# 10-Sensing.net
KiCad netlist of a schematic drawn in Altium Designer
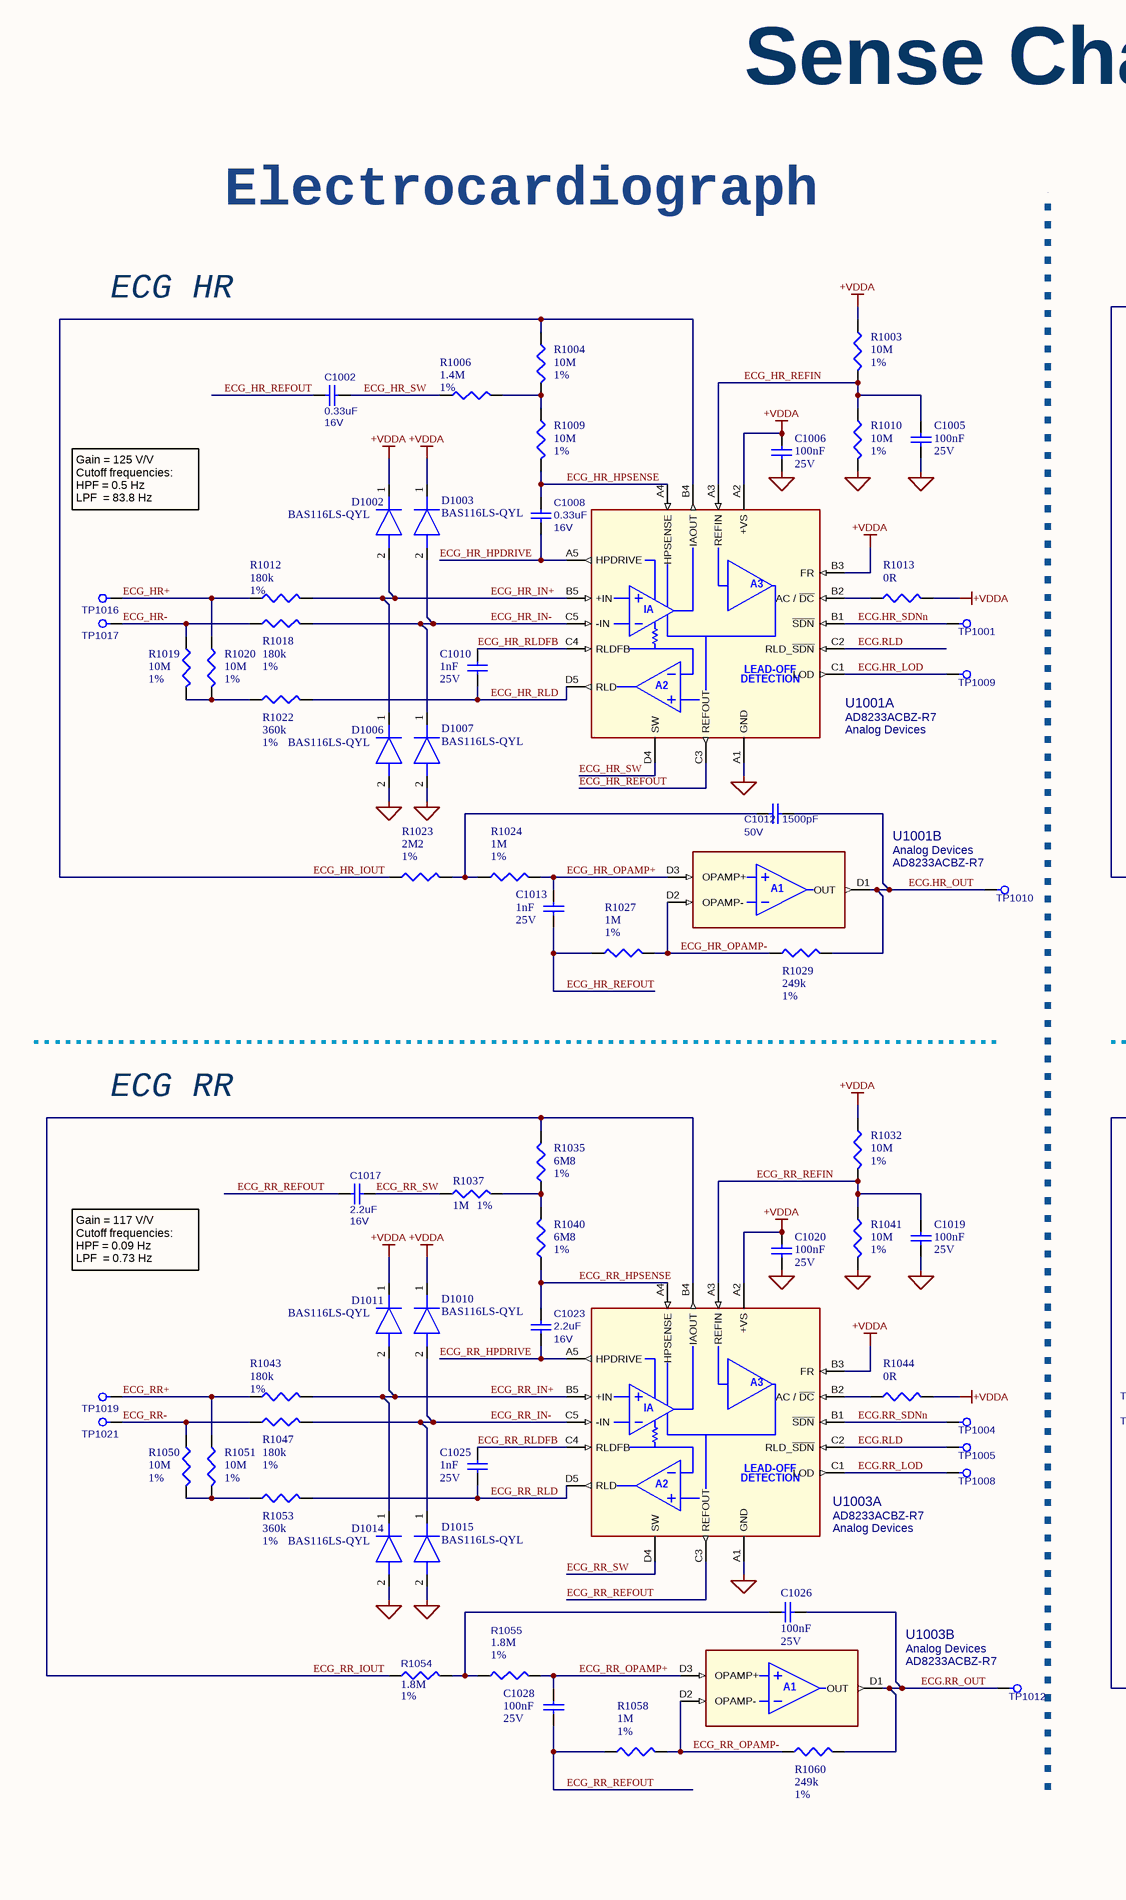
[diagram p0: 10-Sensing.SchDoc, left]
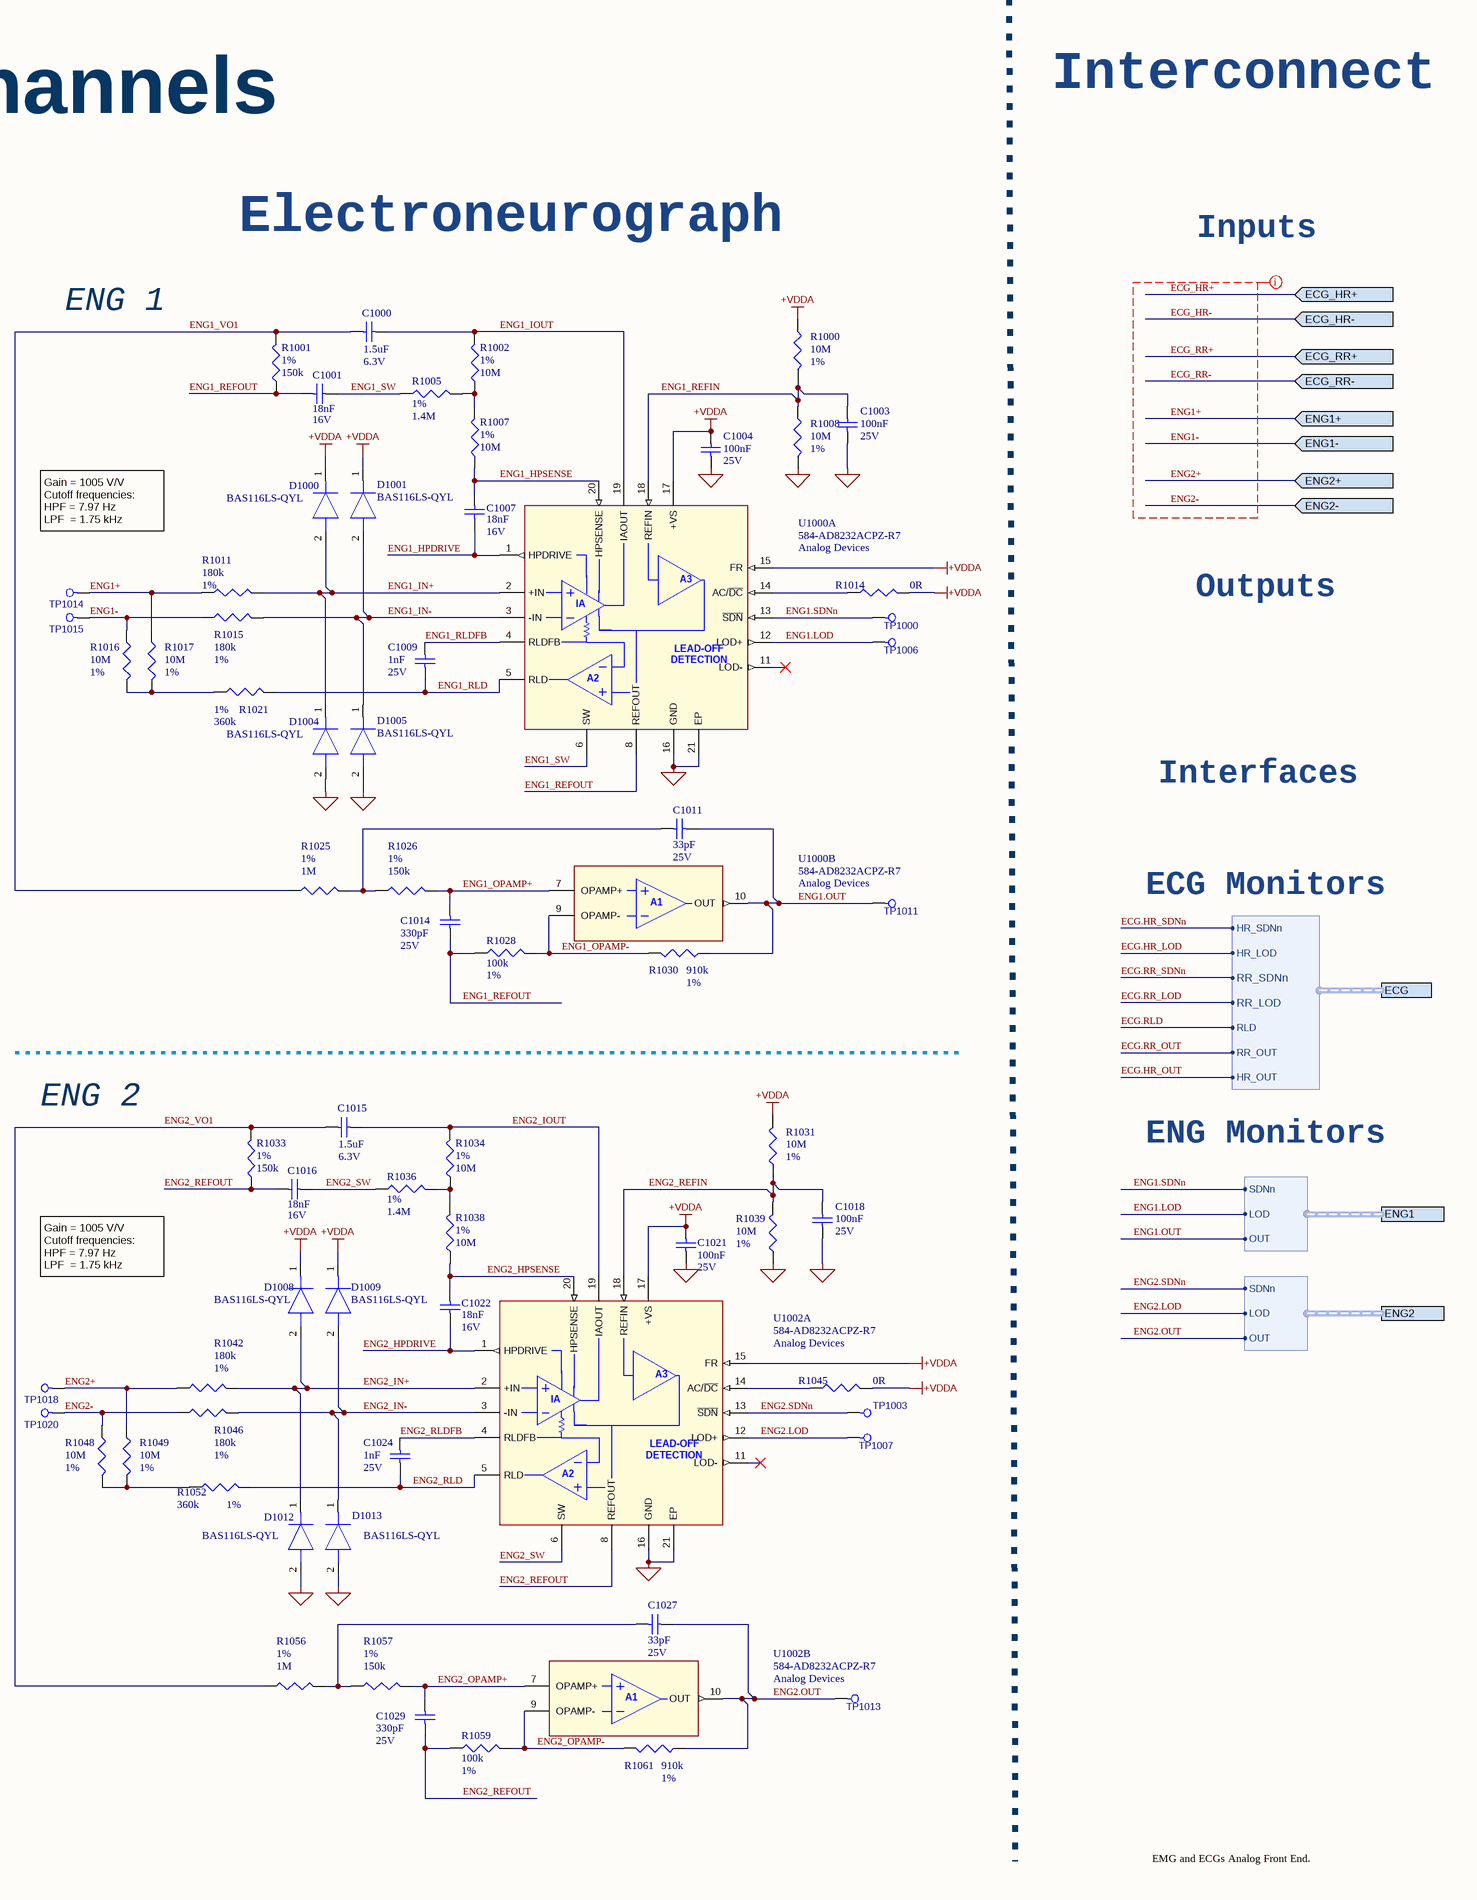
[diagram p1: 10-Sensing.SchDoc, right]

(export (version "E")
  (design (tool "Eeschema 10.0.6"))
  (components
    (comp (ref "C1000")
      (value "1.5uF")
      (footprint "C0201_C")
      (fields
        (field (name "MANUFACTURER") "Murata")
        (field (name "MANUFACTURER PART NUMBER") "GRM033R60J155ME14D")
        (field (name "RATED DC VOLTAGE (URDC)") "6.3V")
      )
      (libsource (lib "MP-LIBRARY") (part "GRM033R60J155ME14D"))
    )
    (comp (ref "C1001")
      (value "18nF")
      (footprint "C0201_C")
      (fields
        (field (name "MANUFACTURER") "Murata")
        (field (name "MANUFACTURER PART NUMBER") "GRM033R61C183KE84D")
        (field (name "RATED DC VOLTAGE (URDC)") "16V")
      )
      (libsource (lib "MP-LIBRARY") (part "GRM033R61C183KE84D"))
    )
    (comp (ref "C1002")
      (value "0.33uF")
      (footprint "CAP0402_REDUCED")
      (description "Capacitor, 0.33uF, X7S, 16V, 10%, 0402")
      (fields
        (field (name "MANUFACTURER") "TDK")
        (field (name "RATING") "16V")
        (field (name "MANUFACTURER PART NUMBER") "CGA2B1X7S1C334K050BC")
      )
      (libsource (lib "MP-LIBRARY") (part "CGA2B1X7S1C334K050BC"))
    )
    (comp (ref "C1003")
      (value "100nF")
      (footprint "C0201_C")
      (fields
        (field (name "MANUFACTURER") "Murata")
        (field (name "MANUFACTURER PART NUMBER") "GRM033R61E104KE14J")
        (field (name "RATED DC VOLTAGE (URDC)") "25V")
      )
      (libsource (lib "MP-LIBRARY") (part "GRM033R61E104KE14J"))
    )
    (comp (ref "C1004")
      (value "100nF")
      (footprint "C0201_C")
      (fields
        (field (name "MANUFACTURER") "Murata")
        (field (name "MANUFACTURER PART NUMBER") "GRM033R61E104KE14J")
        (field (name "RATED DC VOLTAGE (URDC)") "25V")
      )
      (libsource (lib "MP-LIBRARY") (part "GRM033R61E104KE14J"))
    )
    (comp (ref "C1005")
      (value "100nF")
      (footprint "C0201_C")
      (fields
        (field (name "MANUFACTURER") "Murata")
        (field (name "MANUFACTURER PART NUMBER") "GRM033R61E104KE14J")
        (field (name "RATED DC VOLTAGE (URDC)") "25V")
      )
      (libsource (lib "MP-LIBRARY") (part "GRM033R61E104KE14J"))
    )
    (comp (ref "C1006")
      (value "100nF")
      (footprint "C0201_C")
      (fields
        (field (name "MANUFACTURER") "Murata")
        (field (name "MANUFACTURER PART NUMBER") "GRM033R61E104KE14J")
        (field (name "RATED DC VOLTAGE (URDC)") "25V")
      )
      (libsource (lib "MP-LIBRARY") (part "GRM033R61E104KE14J"))
    )
    (comp (ref "C1007")
      (value "18nF")
      (footprint "C0201_C")
      (fields
        (field (name "MANUFACTURER") "Murata")
        (field (name "MANUFACTURER PART NUMBER") "GRM033R61C183KE84D")
        (field (name "RATED DC VOLTAGE (URDC)") "16V")
      )
      (libsource (lib "MP-LIBRARY") (part "GRM033R61C183KE84D"))
    )
    (comp (ref "C1008")
      (value "0.33uF")
      (footprint "CAP0402_REDUCED")
      (description "Capacitor, 0.33uF, X7S, 16V, 10%, 0402")
      (fields
        (field (name "MANUFACTURER") "TDK")
        (field (name "RATING") "16V")
        (field (name "MANUFACTURER PART NUMBER") "CGA2B1X7S1C334K050BC")
      )
      (libsource (lib "MP-LIBRARY") (part "CGA2B1X7S1C334K050BC"))
    )
    (comp (ref "C1009")
      (value "1nF")
      (footprint "C0201_C")
      (fields
        (field (name "MANUFACTURER") "Murata")
        (field (name "MANUFACTURER PART NUMBER") "GRM033R71E102KA01J")
        (field (name "RATED DC VOLTAGE (URDC)") "25V")
      )
      (libsource (lib "MP-LIBRARY") (part "GRM033R71E102KA01J"))
    )
    (comp (ref "C1010")
      (value "1nF")
      (footprint "C0201_C")
      (fields
        (field (name "MANUFACTURER") "Murata")
        (field (name "MANUFACTURER PART NUMBER") "GRM033R71E102KA01J")
        (field (name "RATED DC VOLTAGE (URDC)") "25V")
      )
      (libsource (lib "MP-LIBRARY") (part "GRM033R71E102KA01J"))
    )
    (comp (ref "C1011")
      (value "33pF")
      (footprint "C0201_C")
      (fields
        (field (name "MANUFACTURER") "Murata")
        (field (name "MANUFACTURER PART NUMBER") "GRM0335C1E330JA01D")
        (field (name "RATED DC VOLTAGE (URDC)") "25V")
      )
      (libsource (lib "MP-LIBRARY") (part "GRM0335C1E330JA01D"))
    )
    (comp (ref "C1012")
      (value "1500pF")
      (footprint "CAP0402_REDUCED")
      (description "Capacitor, 1500pF, X7R, 50V, 10%, 0402")
      (fields
        (field (name "MANUFACTURER") "Murata")
        (field (name "RATING") "50V")
        (field (name "MANUFACTURER PART NUMBER") "GCM155R71H152KA37D")
      )
      (libsource (lib "MP-LIBRARY") (part "GCM155R71H152KA37D"))
    )
    (comp (ref "C1013")
      (value "1nF")
      (footprint "C0201_C")
      (fields
        (field (name "MANUFACTURER") "Murata")
        (field (name "MANUFACTURER PART NUMBER") "GRM033R71E102KA01J")
        (field (name "RATED DC VOLTAGE (URDC)") "25V")
      )
      (libsource (lib "MP-LIBRARY") (part "GRM033R71E102KA01J"))
    )
    (comp (ref "C1014")
      (value "330pF")
      (footprint "C0201_C")
      (fields
        (field (name "MANUFACTURER") "Murata")
        (field (name "MANUFACTURER PART NUMBER") "GRM033R71E331KA01D")
        (field (name "RATED DC VOLTAGE (URDC)") "25V")
      )
      (libsource (lib "MP-LIBRARY") (part "GRM033R71E331KA01D"))
    )
    (comp (ref "C1015")
      (value "1.5uF")
      (footprint "C0201_C")
      (fields
        (field (name "MANUFACTURER") "Murata")
        (field (name "MANUFACTURER PART NUMBER") "GRM033R60J155ME14D")
        (field (name "RATED DC VOLTAGE (URDC)") "6.3V")
      )
      (libsource (lib "MP-LIBRARY") (part "GRM033R60J155ME14D"))
    )
    (comp (ref "C1016")
      (value "18nF")
      (footprint "C0201_C")
      (fields
        (field (name "MANUFACTURER") "Murata")
        (field (name "MANUFACTURER PART NUMBER") "GRM033R61C183KE84D")
        (field (name "RATED DC VOLTAGE (URDC)") "16V")
      )
      (libsource (lib "MP-LIBRARY") (part "GRM033R61C183KE84D"))
    )
    (comp (ref "C1017")
      (value "2.2uF")
      (footprint "CAP0603_REDUCED")
      (description "Capacitor, 2.2uF, X7R, 16V, 10%, 0603, Implant-grade")
      (fields
        (field (name "MANUFACTURER") "Murata")
        (field (name "RATING") "16V")
        (field (name "MANUFACTURER PART NUMBER") "GRM188Z71C225ME43J")
      )
      (libsource (lib "MP-LIBRARY") (part "GRM188Z71C225ME43J"))
    )
    (comp (ref "C1018")
      (value "100nF")
      (footprint "C0201_C")
      (fields
        (field (name "MANUFACTURER") "Murata")
        (field (name "MANUFACTURER PART NUMBER") "GRM033R61E104KE14J")
        (field (name "RATED DC VOLTAGE (URDC)") "25V")
      )
      (libsource (lib "MP-LIBRARY") (part "GRM033R61E104KE14J"))
    )
    (comp (ref "C1019")
      (value "100nF")
      (footprint "C0201_C")
      (fields
        (field (name "MANUFACTURER") "Murata")
        (field (name "MANUFACTURER PART NUMBER") "GRM033R61E104KE14J")
        (field (name "RATED DC VOLTAGE (URDC)") "25V")
      )
      (libsource (lib "MP-LIBRARY") (part "GRM033R61E104KE14J"))
    )
    (comp (ref "C1020")
      (value "100nF")
      (footprint "C0201_C")
      (fields
        (field (name "MANUFACTURER") "Murata")
        (field (name "MANUFACTURER PART NUMBER") "GRM033R61E104KE14J")
        (field (name "RATED DC VOLTAGE (URDC)") "25V")
      )
      (libsource (lib "MP-LIBRARY") (part "GRM033R61E104KE14J"))
    )
    (comp (ref "C1021")
      (value "100nF")
      (footprint "C0201_C")
      (fields
        (field (name "MANUFACTURER") "Murata")
        (field (name "MANUFACTURER PART NUMBER") "GRM033R61E104KE14J")
        (field (name "RATED DC VOLTAGE (URDC)") "25V")
      )
      (libsource (lib "MP-LIBRARY") (part "GRM033R61E104KE14J"))
    )
    (comp (ref "C1022")
      (value "18nF")
      (footprint "C0201_C")
      (fields
        (field (name "MANUFACTURER") "Murata")
        (field (name "MANUFACTURER PART NUMBER") "GRM033R61C183KE84D")
        (field (name "RATED DC VOLTAGE (URDC)") "16V")
      )
      (libsource (lib "MP-LIBRARY") (part "GRM033R61C183KE84D"))
    )
    (comp (ref "C1023")
      (value "2.2uF")
      (footprint "CAP0603_REDUCED")
      (description "Capacitor, 2.2uF, X7R, 16V, 10%, 0603, Implant-grade")
      (fields
        (field (name "MANUFACTURER") "Murata")
        (field (name "RATING") "16V")
        (field (name "MANUFACTURER PART NUMBER") "GRM188Z71C225ME43J")
      )
      (libsource (lib "MP-LIBRARY") (part "GRM188Z71C225ME43J"))
    )
    (comp (ref "C1024")
      (value "1nF")
      (footprint "C0201_C")
      (fields
        (field (name "MANUFACTURER") "Murata")
        (field (name "MANUFACTURER PART NUMBER") "GRM033R71E102KA01J")
        (field (name "RATED DC VOLTAGE (URDC)") "25V")
      )
      (libsource (lib "MP-LIBRARY") (part "GRM033R71E102KA01J"))
    )
    (comp (ref "C1025")
      (value "1nF")
      (footprint "C0201_C")
      (fields
        (field (name "MANUFACTURER") "Murata")
        (field (name "MANUFACTURER PART NUMBER") "GRM033R71E102KA01J")
        (field (name "RATED DC VOLTAGE (URDC)") "25V")
      )
      (libsource (lib "MP-LIBRARY") (part "GRM033R71E102KA01J"))
    )
    (comp (ref "C1026")
      (value "100nF")
      (footprint "C0201_C")
      (fields
        (field (name "MANUFACTURER") "Murata")
        (field (name "MANUFACTURER PART NUMBER") "GRM033R61E104KE14J")
        (field (name "RATED DC VOLTAGE (URDC)") "25V")
      )
      (libsource (lib "MP-LIBRARY") (part "GRM033R61E104KE14J"))
    )
    (comp (ref "C1027")
      (value "33pF")
      (footprint "C0201_C")
      (fields
        (field (name "MANUFACTURER") "Murata")
        (field (name "MANUFACTURER PART NUMBER") "GRM0335C1E330JA01D")
        (field (name "RATED DC VOLTAGE (URDC)") "25V")
      )
      (libsource (lib "MP-LIBRARY") (part "GRM0335C1E330JA01D"))
    )
    (comp (ref "C1028")
      (value "100nF")
      (footprint "C0201_C")
      (fields
        (field (name "MANUFACTURER") "Murata")
        (field (name "MANUFACTURER PART NUMBER") "GRM033R61E104KE14J")
        (field (name "RATED DC VOLTAGE (URDC)") "25V")
      )
      (libsource (lib "MP-LIBRARY") (part "GRM033R61E104KE14J"))
    )
    (comp (ref "C1029")
      (value "330pF")
      (footprint "C0201_C")
      (fields
        (field (name "MANUFACTURER") "Murata")
        (field (name "MANUFACTURER PART NUMBER") "GRM033R71E331KA01D")
        (field (name "RATED DC VOLTAGE (URDC)") "25V")
      )
      (libsource (lib "MP-LIBRARY") (part "GRM033R71E331KA01D"))
    )
    (comp (ref "D1000")
      (value "BAS116LS-QYL")
      (footprint "BAS116LSQYL")
      (description "Diode")
      (fields (field (name "MOUSER PART NUMBER") "771-BAS116LS-QYL") (field (name "MANUFACTURER") "Nexperia"))
      (libsource (lib "MP-LIBRARY") (part "BAS116LS-QYL"))
    )
    (comp (ref "D1001")
      (value "BAS116LS-QYL")
      (footprint "BAS116LSQYL")
      (description "Diode")
      (fields (field (name "MOUSER PART NUMBER") "771-BAS116LS-QYL") (field (name "MANUFACTURER") "Nexperia"))
      (libsource (lib "MP-LIBRARY") (part "BAS116LS-QYL"))
    )
    (comp (ref "D1002")
      (value "BAS116LS-QYL")
      (footprint "BAS116LSQYL")
      (description "Diode")
      (fields (field (name "MOUSER PART NUMBER") "771-BAS116LS-QYL") (field (name "MANUFACTURER") "Nexperia"))
      (libsource (lib "MP-LIBRARY") (part "BAS116LS-QYL"))
    )
    (comp (ref "D1003")
      (value "BAS116LS-QYL")
      (footprint "BAS116LSQYL")
      (description "Diode")
      (fields (field (name "MOUSER PART NUMBER") "771-BAS116LS-QYL") (field (name "MANUFACTURER") "Nexperia"))
      (libsource (lib "MP-LIBRARY") (part "BAS116LS-QYL"))
    )
    (comp (ref "D1004")
      (value "BAS116LS-QYL")
      (footprint "BAS116LSQYL")
      (description "Diode")
      (fields (field (name "MOUSER PART NUMBER") "771-BAS116LS-QYL") (field (name "MANUFACTURER") "Nexperia"))
      (libsource (lib "MP-LIBRARY") (part "BAS116LS-QYL"))
    )
    (comp (ref "D1005")
      (value "BAS116LS-QYL")
      (footprint "BAS116LSQYL")
      (description "Diode")
      (fields (field (name "MOUSER PART NUMBER") "771-BAS116LS-QYL") (field (name "MANUFACTURER") "Nexperia"))
      (libsource (lib "MP-LIBRARY") (part "BAS116LS-QYL"))
    )
    (comp (ref "D1006")
      (value "BAS116LS-QYL")
      (footprint "BAS116LSQYL")
      (description "Diode")
      (fields (field (name "MOUSER PART NUMBER") "771-BAS116LS-QYL") (field (name "MANUFACTURER") "Nexperia"))
      (libsource (lib "MP-LIBRARY") (part "BAS116LS-QYL"))
    )
    (comp (ref "D1007")
      (value "BAS116LS-QYL")
      (footprint "BAS116LSQYL")
      (description "Diode")
      (fields (field (name "MOUSER PART NUMBER") "771-BAS116LS-QYL") (field (name "MANUFACTURER") "Nexperia"))
      (libsource (lib "MP-LIBRARY") (part "BAS116LS-QYL"))
    )
    (comp (ref "D1008")
      (value "BAS116LS-QYL")
      (footprint "BAS116LSQYL")
      (description "Diode")
      (fields (field (name "MOUSER PART NUMBER") "771-BAS116LS-QYL") (field (name "MANUFACTURER") "Nexperia"))
      (libsource (lib "MP-LIBRARY") (part "BAS116LS-QYL"))
    )
    (comp (ref "D1009")
      (value "BAS116LS-QYL")
      (footprint "BAS116LSQYL")
      (description "Diode")
      (fields (field (name "MOUSER PART NUMBER") "771-BAS116LS-QYL") (field (name "MANUFACTURER") "Nexperia"))
      (libsource (lib "MP-LIBRARY") (part "BAS116LS-QYL"))
    )
    (comp (ref "D1010")
      (value "BAS116LS-QYL")
      (footprint "BAS116LSQYL")
      (description "Diode")
      (fields (field (name "MOUSER PART NUMBER") "771-BAS116LS-QYL") (field (name "MANUFACTURER") "Nexperia"))
      (libsource (lib "MP-LIBRARY") (part "BAS116LS-QYL"))
    )
    (comp (ref "D1011")
      (value "BAS116LS-QYL")
      (footprint "BAS116LSQYL")
      (description "Diode")
      (fields (field (name "MOUSER PART NUMBER") "771-BAS116LS-QYL") (field (name "MANUFACTURER") "Nexperia"))
      (libsource (lib "MP-LIBRARY") (part "BAS116LS-QYL"))
    )
    (comp (ref "D1012")
      (value "BAS116LS-QYL")
      (footprint "BAS116LSQYL")
      (description "Diode")
      (fields (field (name "MOUSER PART NUMBER") "771-BAS116LS-QYL") (field (name "MANUFACTURER") "Nexperia"))
      (libsource (lib "MP-LIBRARY") (part "BAS116LS-QYL"))
    )
    (comp (ref "D1013")
      (value "BAS116LS-QYL")
      (footprint "BAS116LSQYL")
      (description "Diode")
      (fields (field (name "MOUSER PART NUMBER") "771-BAS116LS-QYL") (field (name "MANUFACTURER") "Nexperia"))
      (libsource (lib "MP-LIBRARY") (part "BAS116LS-QYL"))
    )
    (comp (ref "D1014")
      (value "BAS116LS-QYL")
      (footprint "BAS116LSQYL")
      (description "Diode")
      (fields (field (name "MOUSER PART NUMBER") "771-BAS116LS-QYL") (field (name "MANUFACTURER") "Nexperia"))
      (libsource (lib "MP-LIBRARY") (part "BAS116LS-QYL"))
    )
    (comp (ref "D1015")
      (value "BAS116LS-QYL")
      (footprint "BAS116LSQYL")
      (description "Diode")
      (fields (field (name "MOUSER PART NUMBER") "771-BAS116LS-QYL") (field (name "MANUFACTURER") "Nexperia"))
      (libsource (lib "MP-LIBRARY") (part "BAS116LS-QYL"))
    )
    (comp (ref "R1000")
      (value "10M")
      (footprint "R0201_C")
      (fields
        (field (name "MANUFACTURER") "Vishay Draloric")
        (field (name "MANUFACTURER PART NUMBER") "CRCW020110M0FNED")
        (field (name "TOLERANCE") "1%")
        (field (name "POWER") "50mW")
      )
      (libsource (lib "MP-LIBRARY") (part "CRCW020110M0FNED"))
    )
    (comp (ref "R1001")
      (value "150k")
      (footprint "R0201_C")
      (fields
        (field (name "MANUFACTURER") "Vishay")
        (field (name "MANUFACTURER PART NUMBER") "CRCW0201150KFNED")
        (field (name "TOLERANCE") "1%")
        (field (name "POWER") "50mW")
      )
      (libsource (lib "MP-LIBRARY") (part "CRCW0201150KFNED"))
    )
    (comp (ref "R1002")
      (value "10M")
      (footprint "R0201_C")
      (fields
        (field (name "MANUFACTURER") "Vishay Draloric")
        (field (name "MANUFACTURER PART NUMBER") "CRCW020110M0FNED")
        (field (name "TOLERANCE") "1%")
        (field (name "POWER") "50mW")
      )
      (libsource (lib "MP-LIBRARY") (part "CRCW020110M0FNED"))
    )
    (comp (ref "R1003")
      (value "10M")
      (footprint "R0201_C")
      (fields
        (field (name "MANUFACTURER") "Vishay Draloric")
        (field (name "MANUFACTURER PART NUMBER") "CRCW020110M0FNED")
        (field (name "TOLERANCE") "1%")
        (field (name "POWER") "50mW")
      )
      (libsource (lib "MP-LIBRARY") (part "CRCW020110M0FNED"))
    )
    (comp (ref "R1004")
      (value "10M")
      (footprint "R0201_C")
      (fields
        (field (name "MANUFACTURER") "Vishay Draloric")
        (field (name "MANUFACTURER PART NUMBER") "CRCW020110M0FNED")
        (field (name "TOLERANCE") "1%")
        (field (name "POWER") "50mW")
      )
      (libsource (lib "MP-LIBRARY") (part "CRCW020110M0FNED"))
    )
    (comp (ref "R1005")
      (value "1.4M")
      (footprint "R0201_C")
      (fields
        (field (name "MANUFACTURER") "Vishay Draloric")
        (field (name "MANUFACTURER PART NUMBER") "CRCW02011M40FNED")
        (field (name "TOLERANCE") "1%")
        (field (name "POWER") "50mW")
      )
      (libsource (lib "MP-LIBRARY") (part "CRCW02011M40FNED"))
    )
    (comp (ref "R1006")
      (value "1.4M")
      (footprint "R0201_C")
      (fields
        (field (name "MANUFACTURER") "Vishay Draloric")
        (field (name "MANUFACTURER PART NUMBER") "CRCW02011M40FNED")
        (field (name "TOLERANCE") "1%")
        (field (name "POWER") "50mW")
      )
      (libsource (lib "MP-LIBRARY") (part "CRCW02011M40FNED"))
    )
    (comp (ref "R1007")
      (value "10M")
      (footprint "R0201_C")
      (fields
        (field (name "MANUFACTURER") "Vishay Draloric")
        (field (name "MANUFACTURER PART NUMBER") "CRCW020110M0FNED")
        (field (name "TOLERANCE") "1%")
        (field (name "POWER") "50mW")
      )
      (libsource (lib "MP-LIBRARY") (part "CRCW020110M0FNED"))
    )
    (comp (ref "R1008")
      (value "10M")
      (footprint "R0201_C")
      (fields
        (field (name "MANUFACTURER") "Vishay Draloric")
        (field (name "MANUFACTURER PART NUMBER") "CRCW020110M0FNED")
        (field (name "TOLERANCE") "1%")
        (field (name "POWER") "50mW")
      )
      (libsource (lib "MP-LIBRARY") (part "CRCW020110M0FNED"))
    )
    (comp (ref "R1009")
      (value "10M")
      (footprint "R0201_C")
      (fields
        (field (name "MANUFACTURER") "Vishay Draloric")
        (field (name "MANUFACTURER PART NUMBER") "CRCW020110M0FNED")
        (field (name "TOLERANCE") "1%")
        (field (name "POWER") "50mW")
      )
      (libsource (lib "MP-LIBRARY") (part "CRCW020110M0FNED"))
    )
    (comp (ref "R1010")
      (value "10M")
      (footprint "R0201_C")
      (fields
        (field (name "MANUFACTURER") "Vishay Draloric")
        (field (name "MANUFACTURER PART NUMBER") "CRCW020110M0FNED")
        (field (name "TOLERANCE") "1%")
        (field (name "POWER") "50mW")
      )
      (libsource (lib "MP-LIBRARY") (part "CRCW020110M0FNED"))
    )
    (comp (ref "R1011")
      (value "180k")
      (footprint "R0201_C")
      (fields
        (field (name "MANUFACTURER") "Vishay")
        (field (name "MANUFACTURER PART NUMBER") "CRCW0201180KFNED")
        (field (name "TOLERANCE") "1%")
        (field (name "POWER") "50mW")
      )
      (libsource (lib "MP-LIBRARY") (part "CRCW0201180KFNED"))
    )
    (comp (ref "R1012")
      (value "180k")
      (footprint "R0201_C")
      (fields
        (field (name "MANUFACTURER") "Vishay")
        (field (name "MANUFACTURER PART NUMBER") "CRCW0201180KFNED")
        (field (name "TOLERANCE") "1%")
        (field (name "POWER") "50mW")
      )
      (libsource (lib "MP-LIBRARY") (part "CRCW0201180KFNED"))
    )
    (comp (ref "R1013")
      (value "0R")
      (footprint "R0201_C")
      (description "Fixed Resistor, Metal Glaze/thick Film, 0.05W, 0ohm, Surface Mount, 0201")
      (fields
        (field (name "MANUFACTURER") "Vishay")
        (field (name "MANUFACTURER PART NUMBER") "CRCW02010000Z0ED")
      )
      (libsource (lib "MP-LIBRARY") (part "CRCW02010000Z0ED"))
    )
    (comp (ref "R1014")
      (value "0R")
      (footprint "R0201_C")
      (description "Fixed Resistor, Metal Glaze/thick Film, 0.05W, 0ohm, Surface Mount, 0201")
      (fields
        (field (name "MANUFACTURER") "Vishay")
        (field (name "MANUFACTURER PART NUMBER") "CRCW02010000Z0ED")
      )
      (libsource (lib "MP-LIBRARY") (part "CRCW02010000Z0ED"))
    )
    (comp (ref "R1015")
      (value "180k")
      (footprint "R0201_C")
      (fields
        (field (name "MANUFACTURER") "Vishay")
        (field (name "MANUFACTURER PART NUMBER") "CRCW0201180KFNED")
        (field (name "TOLERANCE") "1%")
        (field (name "POWER") "50mW")
      )
      (libsource (lib "MP-LIBRARY") (part "CRCW0201180KFNED"))
    )
    (comp (ref "R1016")
      (value "10M")
      (footprint "R0201_C")
      (fields
        (field (name "MANUFACTURER") "Vishay Draloric")
        (field (name "MANUFACTURER PART NUMBER") "CRCW020110M0FNED")
        (field (name "TOLERANCE") "1%")
        (field (name "POWER") "50mW")
      )
      (libsource (lib "MP-LIBRARY") (part "CRCW020110M0FNED"))
    )
    (comp (ref "R1017")
      (value "10M")
      (footprint "R0201_C")
      (fields
        (field (name "MANUFACTURER") "Vishay Draloric")
        (field (name "MANUFACTURER PART NUMBER") "CRCW020110M0FNED")
        (field (name "TOLERANCE") "1%")
        (field (name "POWER") "50mW")
      )
      (libsource (lib "MP-LIBRARY") (part "CRCW020110M0FNED"))
    )
    (comp (ref "R1018")
      (value "180k")
      (footprint "R0201_C")
      (fields
        (field (name "MANUFACTURER") "Vishay")
        (field (name "MANUFACTURER PART NUMBER") "CRCW0201180KFNED")
        (field (name "TOLERANCE") "1%")
        (field (name "POWER") "50mW")
      )
      (libsource (lib "MP-LIBRARY") (part "CRCW0201180KFNED"))
    )
    (comp (ref "R1019")
      (value "10M")
      (footprint "R0201_C")
      (fields
        (field (name "MANUFACTURER") "Vishay Draloric")
        (field (name "MANUFACTURER PART NUMBER") "CRCW020110M0FNED")
        (field (name "TOLERANCE") "1%")
        (field (name "POWER") "50mW")
      )
      (libsource (lib "MP-LIBRARY") (part "CRCW020110M0FNED"))
    )
    (comp (ref "R1020")
      (value "10M")
      (footprint "R0201_C")
      (fields
        (field (name "MANUFACTURER") "Vishay Draloric")
        (field (name "MANUFACTURER PART NUMBER") "CRCW020110M0FNED")
        (field (name "TOLERANCE") "1%")
        (field (name "POWER") "50mW")
      )
      (libsource (lib "MP-LIBRARY") (part "CRCW020110M0FNED"))
    )
    (comp (ref "R1021")
      (value "360k")
      (footprint "R0201_C")
      (fields
        (field (name "MANUFACTURER") "Vishay")
        (field (name "MANUFACTURER PART NUMBER") "CRCW0201360KFNED")
        (field (name "TOLERANCE") "1%")
        (field (name "POWER") "50mW")
      )
      (libsource (lib "MP-LIBRARY") (part "CRCW0201360KFNED"))
    )
    (comp (ref "R1022")
      (value "360k")
      (footprint "R0201_C")
      (fields
        (field (name "MANUFACTURER") "Vishay")
        (field (name "MANUFACTURER PART NUMBER") "CRCW0201360KFNED")
        (field (name "TOLERANCE") "1%")
        (field (name "POWER") "50mW")
      )
      (libsource (lib "MP-LIBRARY") (part "CRCW0201360KFNED"))
    )
    (comp (ref "R1023")
      (value "2M2")
      (footprint "R0201_C")
      (fields
        (field (name "MANUFACTURER") "Vishay Draloric")
        (field (name "MANUFACTURER PART NUMBER") "CRCW02012M20FNED")
        (field (name "TOLERANCE") "1%")
        (field (name "POWER") "50mW")
      )
      (libsource (lib "MP-LIBRARY") (part "CRCW02012M20FNED"))
    )
    (comp (ref "R1024")
      (value "1M")
      (footprint "R0201_C")
      (fields
        (field (name "MANUFACTURER") "Vishay")
        (field (name "MANUFACTURER PART NUMBER") "CRCW02011M00FNED")
        (field (name "TOLERANCE") "1%")
        (field (name "POWER") "50mW")
      )
      (libsource (lib "MP-LIBRARY") (part "CRCW02011M00FNED"))
    )
    (comp (ref "R1025")
      (value "1M")
      (footprint "R0201_C")
      (fields
        (field (name "MANUFACTURER") "Vishay")
        (field (name "MANUFACTURER PART NUMBER") "CRCW02011M00FNED")
        (field (name "TOLERANCE") "1%")
        (field (name "POWER") "50mW")
      )
      (libsource (lib "MP-LIBRARY") (part "CRCW02011M00FNED"))
    )
    (comp (ref "R1026")
      (value "150k")
      (footprint "R0201_C")
      (fields
        (field (name "MANUFACTURER") "Vishay")
        (field (name "MANUFACTURER PART NUMBER") "CRCW0201150KFNED")
        (field (name "TOLERANCE") "1%")
        (field (name "POWER") "50mW")
      )
      (libsource (lib "MP-LIBRARY") (part "CRCW0201150KFNED"))
    )
    (comp (ref "R1027")
      (value "1M")
      (footprint "R0201_C")
      (fields
        (field (name "MANUFACTURER") "Vishay")
        (field (name "MANUFACTURER PART NUMBER") "CRCW02011M00FNED")
        (field (name "TOLERANCE") "1%")
        (field (name "POWER") "50mW")
      )
      (libsource (lib "MP-LIBRARY") (part "CRCW02011M00FNED"))
    )
    (comp (ref "R1028")
      (value "100k")
      (footprint "R0201_C")
      (fields
        (field (name "MANUFACTURER") "Vishay")
        (field (name "MANUFACTURER PART NUMBER") "CRCW0201100KFNED")
        (field (name "TOLERANCE") "1%")
        (field (name "POWER") "50mW")
      )
      (libsource (lib "MP-LIBRARY") (part "CRCW0201100KFNED"))
    )
    (comp (ref "R1029")
      (value "249k")
      (footprint "R0201_C")
      (fields
        (field (name "MANUFACTURER") "Vishay")
        (field (name "MANUFACTURER PART NUMBER") "CRCW0201249KFNED")
        (field (name "TOLERANCE") "1%")
        (field (name "POWER") "50mW")
      )
      (libsource (lib "MP-LIBRARY") (part "CRCW0201249KFNED"))
    )
    (comp (ref "R1030")
      (value "910k")
      (footprint "R0201_C")
      (fields
        (field (name "MANUFACTURER") "Vishay Draloric")
        (field (name "MANUFACTURER PART NUMBER") "CRCW0201910KFNED")
        (field (name "TOLERANCE") "1%")
        (field (name "POWER") "50mW")
      )
      (libsource (lib "MP-LIBRARY") (part "CRCW0201910KFNED"))
    )
    (comp (ref "R1031")
      (value "10M")
      (footprint "R0201_C")
      (fields
        (field (name "MANUFACTURER") "Vishay Draloric")
        (field (name "MANUFACTURER PART NUMBER") "CRCW020110M0FNED")
        (field (name "TOLERANCE") "1%")
        (field (name "POWER") "50mW")
      )
      (libsource (lib "MP-LIBRARY") (part "CRCW020110M0FNED"))
    )
    (comp (ref "R1032")
      (value "10M")
      (footprint "R0201_C")
      (fields
        (field (name "MANUFACTURER") "Vishay Draloric")
        (field (name "MANUFACTURER PART NUMBER") "CRCW020110M0FNED")
        (field (name "TOLERANCE") "1%")
        (field (name "POWER") "50mW")
      )
      (libsource (lib "MP-LIBRARY") (part "CRCW020110M0FNED"))
    )
    (comp (ref "R1033")
      (value "150k")
      (footprint "R0201_C")
      (fields
        (field (name "MANUFACTURER") "Vishay")
        (field (name "MANUFACTURER PART NUMBER") "CRCW0201150KFNED")
        (field (name "TOLERANCE") "1%")
        (field (name "POWER") "50mW")
      )
      (libsource (lib "MP-LIBRARY") (part "CRCW0201150KFNED"))
    )
    (comp (ref "R1034")
      (value "10M")
      (footprint "R0201_C")
      (fields
        (field (name "MANUFACTURER") "Vishay Draloric")
        (field (name "MANUFACTURER PART NUMBER") "CRCW020110M0FNED")
        (field (name "TOLERANCE") "1%")
        (field (name "POWER") "50mW")
      )
      (libsource (lib "MP-LIBRARY") (part "CRCW020110M0FNED"))
    )
    (comp (ref "R1035")
      (value "6M8")
      (footprint "R0201_C")
      (fields
        (field (name "MANUFACTURER") "Vishay Draloric")
        (field (name "MANUFACTURER PART NUMBER") "CRCW02016M80FNED")
        (field (name "TOLERANCE") "1%")
        (field (name "POWER") "50mW")
      )
      (libsource (lib "MP-LIBRARY") (part "CRCW02016M80FNED"))
    )
    (comp (ref "R1036")
      (value "1.4M")
      (footprint "R0201_C")
      (fields
        (field (name "MANUFACTURER") "Vishay Draloric")
        (field (name "MANUFACTURER PART NUMBER") "CRCW02011M40FNED")
        (field (name "TOLERANCE") "1%")
        (field (name "POWER") "50mW")
      )
      (libsource (lib "MP-LIBRARY") (part "CRCW02011M40FNED"))
    )
    (comp (ref "R1037")
      (value "1M")
      (footprint "R0201_C")
      (fields
        (field (name "MANUFACTURER") "Vishay")
        (field (name "MANUFACTURER PART NUMBER") "CRCW02011M00FNED")
        (field (name "TOLERANCE") "1%")
        (field (name "POWER") "50mW")
      )
      (libsource (lib "MP-LIBRARY") (part "CRCW02011M00FNED"))
    )
    (comp (ref "R1038")
      (value "10M")
      (footprint "R0201_C")
      (fields
        (field (name "MANUFACTURER") "Vishay Draloric")
        (field (name "MANUFACTURER PART NUMBER") "CRCW020110M0FNED")
        (field (name "TOLERANCE") "1%")
        (field (name "POWER") "50mW")
      )
      (libsource (lib "MP-LIBRARY") (part "CRCW020110M0FNED"))
    )
    (comp (ref "R1039")
      (value "10M")
      (footprint "R0201_C")
      (fields
        (field (name "MANUFACTURER") "Vishay Draloric")
        (field (name "MANUFACTURER PART NUMBER") "CRCW020110M0FNED")
        (field (name "TOLERANCE") "1%")
        (field (name "POWER") "50mW")
      )
      (libsource (lib "MP-LIBRARY") (part "CRCW020110M0FNED"))
    )
    (comp (ref "R1040")
      (value "6M8")
      (footprint "R0201_C")
      (fields
        (field (name "MANUFACTURER") "Vishay Draloric")
        (field (name "MANUFACTURER PART NUMBER") "CRCW02016M80FNED")
        (field (name "TOLERANCE") "1%")
        (field (name "POWER") "50mW")
      )
      (libsource (lib "MP-LIBRARY") (part "CRCW02016M80FNED"))
    )
    (comp (ref "R1041")
      (value "10M")
      (footprint "R0201_C")
      (fields
        (field (name "MANUFACTURER") "Vishay Draloric")
        (field (name "MANUFACTURER PART NUMBER") "CRCW020110M0FNED")
        (field (name "TOLERANCE") "1%")
        (field (name "POWER") "50mW")
      )
      (libsource (lib "MP-LIBRARY") (part "CRCW020110M0FNED"))
    )
    (comp (ref "R1042")
      (value "180k")
      (footprint "R0201_C")
      (fields
        (field (name "MANUFACTURER") "Vishay")
        (field (name "MANUFACTURER PART NUMBER") "CRCW0201180KFNED")
        (field (name "TOLERANCE") "1%")
        (field (name "POWER") "50mW")
      )
      (libsource (lib "MP-LIBRARY") (part "CRCW0201180KFNED"))
    )
    (comp (ref "R1043")
      (value "180k")
      (footprint "R0201_C")
      (fields
        (field (name "MANUFACTURER") "Vishay")
        (field (name "MANUFACTURER PART NUMBER") "CRCW0201180KFNED")
        (field (name "TOLERANCE") "1%")
        (field (name "POWER") "50mW")
      )
      (libsource (lib "MP-LIBRARY") (part "CRCW0201180KFNED"))
    )
    (comp (ref "R1044")
      (value "0R")
      (footprint "R0201_C")
      (description "Fixed Resistor, Metal Glaze/thick Film, 0.05W, 0ohm, Surface Mount, 0201")
      (fields
        (field (name "MANUFACTURER") "Vishay")
        (field (name "MANUFACTURER PART NUMBER") "CRCW02010000Z0ED")
      )
      (libsource (lib "MP-LIBRARY") (part "CRCW02010000Z0ED"))
    )
    (comp (ref "R1045")
      (value "0R")
      (footprint "R0201_C")
      (description "Fixed Resistor, Metal Glaze/thick Film, 0.05W, 0ohm, Surface Mount, 0201")
      (fields
        (field (name "MANUFACTURER") "Vishay")
        (field (name "MANUFACTURER PART NUMBER") "CRCW02010000Z0ED")
      )
      (libsource (lib "MP-LIBRARY") (part "CRCW02010000Z0ED"))
    )
    (comp (ref "R1046")
      (value "180k")
      (footprint "R0201_C")
      (fields
        (field (name "MANUFACTURER") "Vishay")
        (field (name "MANUFACTURER PART NUMBER") "CRCW0201180KFNED")
        (field (name "TOLERANCE") "1%")
        (field (name "POWER") "50mW")
      )
      (libsource (lib "MP-LIBRARY") (part "CRCW0201180KFNED"))
    )
    (comp (ref "R1047")
      (value "180k")
      (footprint "R0201_C")
      (fields
        (field (name "MANUFACTURER") "Vishay")
        (field (name "MANUFACTURER PART NUMBER") "CRCW0201180KFNED")
        (field (name "TOLERANCE") "1%")
        (field (name "POWER") "50mW")
      )
      (libsource (lib "MP-LIBRARY") (part "CRCW0201180KFNED"))
    )
    (comp (ref "R1048")
      (value "10M")
      (footprint "R0201_C")
      (fields
        (field (name "MANUFACTURER") "Vishay Draloric")
        (field (name "MANUFACTURER PART NUMBER") "CRCW020110M0FNED")
        (field (name "TOLERANCE") "1%")
        (field (name "POWER") "50mW")
      )
      (libsource (lib "MP-LIBRARY") (part "CRCW020110M0FNED"))
    )
    (comp (ref "R1049")
      (value "10M")
      (footprint "R0201_C")
      (fields
        (field (name "MANUFACTURER") "Vishay Draloric")
        (field (name "MANUFACTURER PART NUMBER") "CRCW020110M0FNED")
        (field (name "TOLERANCE") "1%")
        (field (name "POWER") "50mW")
      )
      (libsource (lib "MP-LIBRARY") (part "CRCW020110M0FNED"))
    )
    (comp (ref "R1050")
      (value "10M")
      (footprint "R0201_C")
      (fields
        (field (name "MANUFACTURER") "Vishay Draloric")
        (field (name "MANUFACTURER PART NUMBER") "CRCW020110M0FNED")
        (field (name "TOLERANCE") "1%")
        (field (name "POWER") "50mW")
      )
      (libsource (lib "MP-LIBRARY") (part "CRCW020110M0FNED"))
    )
    (comp (ref "R1051")
      (value "10M")
      (footprint "R0201_C")
      (fields
        (field (name "MANUFACTURER") "Vishay Draloric")
        (field (name "MANUFACTURER PART NUMBER") "CRCW020110M0FNED")
        (field (name "TOLERANCE") "1%")
        (field (name "POWER") "50mW")
      )
      (libsource (lib "MP-LIBRARY") (part "CRCW020110M0FNED"))
    )
    (comp (ref "R1052")
      (value "360k")
      (footprint "R0201_C")
      (fields
        (field (name "MANUFACTURER") "Vishay")
        (field (name "MANUFACTURER PART NUMBER") "CRCW0201360KFNED")
        (field (name "TOLERANCE") "1%")
        (field (name "POWER") "50mW")
      )
      (libsource (lib "MP-LIBRARY") (part "CRCW0201360KFNED"))
    )
    (comp (ref "R1053")
      (value "360k")
      (footprint "R0201_C")
      (fields
        (field (name "MANUFACTURER") "Vishay")
        (field (name "MANUFACTURER PART NUMBER") "CRCW0201360KFNED")
        (field (name "TOLERANCE") "1%")
        (field (name "POWER") "50mW")
      )
      (libsource (lib "MP-LIBRARY") (part "CRCW0201360KFNED"))
    )
    (comp (ref "R1054")
      (value "1.8M")
      (footprint "R0201_C")
      (description "Resistor, 1.8M, 1%, 0201")
      (fields
        (field (name "MANUFACTURER") "Yageo")
        (field (name "MANUFACTURER PART NUMBER") "RC0201FR-071M8L")
        (field (name "PRECISION") "1%")
      )
      (libsource (lib "MP-LIBRARY") (part "RC0201FR-071M8L"))
    )
    (comp (ref "R1055")
      (value "1.8M")
      (footprint "R0201_C")
      (description "Resistor, 1.8M, 1%, 0201")
      (fields
        (field (name "MANUFACTURER") "Yageo")
        (field (name "MANUFACTURER PART NUMBER") "RC0201FR-071M8L")
        (field (name "PRECISION") "1%")
      )
      (libsource (lib "MP-LIBRARY") (part "RC0201FR-071M8L"))
    )
    (comp (ref "R1056")
      (value "1M")
      (footprint "R0201_C")
      (fields
        (field (name "MANUFACTURER") "Vishay")
        (field (name "MANUFACTURER PART NUMBER") "CRCW02011M00FNED")
        (field (name "TOLERANCE") "1%")
        (field (name "POWER") "50mW")
      )
      (libsource (lib "MP-LIBRARY") (part "CRCW02011M00FNED"))
    )
    (comp (ref "R1057")
      (value "150k")
      (footprint "R0201_C")
      (fields
        (field (name "MANUFACTURER") "Vishay")
        (field (name "MANUFACTURER PART NUMBER") "CRCW0201150KFNED")
        (field (name "TOLERANCE") "1%")
        (field (name "POWER") "50mW")
      )
      (libsource (lib "MP-LIBRARY") (part "CRCW0201150KFNED"))
    )
    (comp (ref "R1058")
      (value "1M")
      (footprint "R0201_C")
      (fields
        (field (name "MANUFACTURER") "Vishay")
        (field (name "MANUFACTURER PART NUMBER") "CRCW02011M00FNED")
        (field (name "TOLERANCE") "1%")
        (field (name "POWER") "50mW")
      )
      (libsource (lib "MP-LIBRARY") (part "CRCW02011M00FNED"))
    )
    (comp (ref "R1059")
      (value "100k")
      (footprint "R0201_C")
      (fields
        (field (name "MANUFACTURER") "Vishay")
        (field (name "MANUFACTURER PART NUMBER") "CRCW0201100KFNED")
        (field (name "TOLERANCE") "1%")
        (field (name "POWER") "50mW")
      )
      (libsource (lib "MP-LIBRARY") (part "CRCW0201100KFNED"))
    )
    (comp (ref "R1060")
      (value "249k")
      (footprint "R0201_C")
      (fields
        (field (name "MANUFACTURER") "Vishay")
        (field (name "MANUFACTURER PART NUMBER") "CRCW0201249KFNED")
        (field (name "TOLERANCE") "1%")
        (field (name "POWER") "50mW")
      )
      (libsource (lib "MP-LIBRARY") (part "CRCW0201249KFNED"))
    )
    (comp (ref "R1061")
      (value "910k")
      (footprint "R0201_C")
      (fields
        (field (name "MANUFACTURER") "Vishay Draloric")
        (field (name "MANUFACTURER PART NUMBER") "CRCW0201910KFNED")
        (field (name "TOLERANCE") "1%")
        (field (name "POWER") "50mW")
      )
      (libsource (lib "MP-LIBRARY") (part "CRCW0201910KFNED"))
    )
    (comp (ref "TP1000")
      (value "Test Point")
      (footprint "testpad_0.9mm")
      (description "Test pad, 0.90mm circular pad")
      (libsource (lib "MP-LIBRARY") (part "Test Point"))
    )
    (comp (ref "TP1001")
      (value "Test Point")
      (footprint "testpad_0.9mm")
      (description "Test pad, 0.90mm circular pad")
      (libsource (lib "MP-LIBRARY") (part "Test Point"))
    )
    (comp (ref "TP1003")
      (value "Test Point")
      (footprint "testpad_0.9mm")
      (description "Test pad, 0.90mm circular pad")
      (libsource (lib "MP-LIBRARY") (part "Test Point"))
    )
    (comp (ref "TP1004")
      (value "Test Point")
      (footprint "testpad_0.9mm")
      (description "Test pad, 0.90mm circular pad")
      (libsource (lib "MP-LIBRARY") (part "Test Point"))
    )
    (comp (ref "TP1005")
      (value "Test Point")
      (footprint "testpad_0.9mm")
      (description "Test pad, 0.90mm circular pad")
      (libsource (lib "MP-LIBRARY") (part "Test Point"))
    )
    (comp (ref "TP1006")
      (value "Test Point")
      (footprint "testpad_0.9mm")
      (description "Test pad, 0.90mm circular pad")
      (libsource (lib "MP-LIBRARY") (part "Test Point"))
    )
    (comp (ref "TP1007")
      (value "Test Point")
      (footprint "testpad_0.9mm")
      (description "Test pad, 0.90mm circular pad")
      (libsource (lib "MP-LIBRARY") (part "Test Point"))
    )
    (comp (ref "TP1008")
      (value "Test Point")
      (footprint "testpad_0.9mm")
      (description "Test pad, 0.90mm circular pad")
      (libsource (lib "MP-LIBRARY") (part "Test Point"))
    )
    (comp (ref "TP1009")
      (value "Test Point")
      (footprint "testpad_0.9mm")
      (description "Test pad, 0.90mm circular pad")
      (libsource (lib "MP-LIBRARY") (part "Test Point"))
    )
    (comp (ref "TP1010")
      (value "Test Point")
      (footprint "testpad_0.9mm")
      (description "Test pad, 0.90mm circular pad")
      (libsource (lib "MP-LIBRARY") (part "Test Point"))
    )
    (comp (ref "TP1011")
      (value "Test Point")
      (footprint "testpad_0.9mm")
      (description "Test pad, 0.90mm circular pad")
      (libsource (lib "MP-LIBRARY") (part "Test Point"))
    )
    (comp (ref "TP1012")
      (value "Test Point")
      (footprint "testpad_0.9mm")
      (description "Test pad, 0.90mm circular pad")
      (libsource (lib "MP-LIBRARY") (part "Test Point"))
    )
    (comp (ref "TP1013")
      (value "Test Point")
      (footprint "testpad_0.9mm")
      (description "Test pad, 0.90mm circular pad")
      (libsource (lib "MP-LIBRARY") (part "Test Point"))
    )
    (comp (ref "TP1014")
      (value "Test Point")
      (footprint "testpad_0.9mm")
      (description "Test pad, 0.90mm circular pad")
      (libsource (lib "MP-LIBRARY") (part "Test Point"))
    )
    (comp (ref "TP1015")
      (value "Test Point")
      (footprint "testpad_0.9mm")
      (description "Test pad, 0.90mm circular pad")
      (libsource (lib "MP-LIBRARY") (part "Test Point"))
    )
    (comp (ref "TP1016")
      (value "Test Point")
      (footprint "testpad_0.9mm")
      (description "Test pad, 0.90mm circular pad")
      (libsource (lib "MP-LIBRARY") (part "Test Point"))
    )
    (comp (ref "TP1017")
      (value "Test Point")
      (footprint "testpad_0.9mm")
      (description "Test pad, 0.90mm circular pad")
      (libsource (lib "MP-LIBRARY") (part "Test Point"))
    )
    (comp (ref "TP1018")
      (value "Test Point")
      (footprint "testpad_0.9mm")
      (description "Test pad, 0.90mm circular pad")
      (libsource (lib "MP-LIBRARY") (part "Test Point"))
    )
    (comp (ref "TP1019")
      (value "Test Point")
      (footprint "testpad_0.9mm")
      (description "Test pad, 0.90mm circular pad")
      (libsource (lib "MP-LIBRARY") (part "Test Point"))
    )
    (comp (ref "TP1020")
      (value "Test Point")
      (footprint "testpad_0.9mm")
      (description "Test pad, 0.90mm circular pad")
      (libsource (lib "MP-LIBRARY") (part "Test Point"))
    )
    (comp (ref "TP1021")
      (value "Test Point")
      (footprint "testpad_0.9mm")
      (description "Test pad, 0.90mm circular pad")
      (libsource (lib "MP-LIBRARY") (part "Test Point"))
    )
    (comp (ref "U1000")
      (value "AD8232ACPZ-R7")
      (footprint "FP-CP-20-8-IPC_C")
      (description "Analog Circuit, 1 Func, 1 Channel")
      (fields
        (field (name "SUPPLIER PART NUMBER") "584-AD8232ACPZ-R7")
        (field (name "MANUFACTURER") "Analog Devices")
      )
      (libsource (lib "MP-LIBRARY") (part "AD8232ACPZ-R7"))
    )
    (comp (ref "U1001")
      (value "AD8233ACBZ-R7")
      (footprint "AD8233ACBZ-R7")
      (description "Analog front end, ECG, RLD amp, BGA-20")
      (fields (field (name "MANUFACTURER") "Analog Devices"))
      (libsource (lib "MP-LIBRARY") (part "AD8233ACBZ-R7"))
    )
    (comp (ref "U1002")
      (value "AD8232ACPZ-R7")
      (footprint "FP-CP-20-8-IPC_C")
      (description "Analog Circuit, 1 Func, 1 Channel")
      (fields
        (field (name "SUPPLIER PART NUMBER") "584-AD8232ACPZ-R7")
        (field (name "MANUFACTURER") "Analog Devices")
      )
      (libsource (lib "MP-LIBRARY") (part "AD8232ACPZ-R7"))
    )
    (comp (ref "U1003")
      (value "AD8233ACBZ-R7")
      (footprint "AD8233ACBZ-R7")
      (description "Analog front end, ECG, RLD amp, BGA-20")
      (fields (field (name "MANUFACTURER") "Analog Devices"))
      (libsource (lib "MP-LIBRARY") (part "AD8233ACBZ-R7"))
    )
  )
  (nets
    (net (code "3") (name "+VDDA") (class "Default")
      (node (ref "C1004") (pin "2") (pinfunction "2_2") (pintype "passive"))
      (node (ref "C1006") (pin "2") (pinfunction "2_2") (pintype "passive"))
      (node (ref "C1020") (pin "2") (pinfunction "2_2") (pintype "passive"))
      (node (ref "C1021") (pin "1") (pinfunction "1_1") (pintype "passive"))
      (node (ref "D1000") (pin "1") (pinfunction "K_1") (pintype "passive"))
      (node (ref "D1001") (pin "1") (pinfunction "K_1") (pintype "passive"))
      (node (ref "D1002") (pin "1") (pinfunction "K_1") (pintype "passive"))
      (node (ref "D1003") (pin "1") (pinfunction "K_1") (pintype "passive"))
      (node (ref "D1008") (pin "1") (pinfunction "K_1") (pintype "passive"))
      (node (ref "D1009") (pin "1") (pinfunction "K_1") (pintype "passive"))
      (node (ref "D1010") (pin "1") (pinfunction "K_1") (pintype "passive"))
      (node (ref "D1011") (pin "1") (pinfunction "K_1") (pintype "passive"))
      (node (ref "R1000") (pin "1") (pinfunction "1_1") (pintype "passive"))
      (node (ref "R1003") (pin "1") (pinfunction "1_1") (pintype "passive"))
      (node (ref "R1013") (pin "2") (pinfunction "2_2") (pintype "passive"))
      (node (ref "R1014") (pin "2") (pinfunction "2_2") (pintype "passive"))
      (node (ref "R1031") (pin "2") (pinfunction "2_2") (pintype "passive"))
      (node (ref "R1032") (pin "1") (pinfunction "1_1") (pintype "passive"))
      (node (ref "R1044") (pin "2") (pinfunction "2_2") (pintype "passive"))
      (node (ref "R1045") (pin "2") (pinfunction "2_2") (pintype "passive"))
      (node (ref "U1000") (pin "15") (pinfunction "FR_15") (pintype "input"))
      (node (ref "U1000") (pin "17") (pinfunction "+VS_17") (pintype "power_in"))
      (node (ref "U1001") (pin "A2") (pinfunction "+VS_A2") (pintype "power_in"))
      (node (ref "U1001") (pin "B3") (pinfunction "FR_B3") (pintype "input"))
      (node (ref "U1002") (pin "15") (pinfunction "FR_15") (pintype "input"))
      (node (ref "U1002") (pin "17") (pinfunction "+VS_17") (pintype "power_in"))
      (node (ref "U1003") (pin "A2") (pinfunction "+VS_A2") (pintype "power_in"))
      (node (ref "U1003") (pin "B3") (pinfunction "FR_B3") (pintype "input"))
    )
    (net (code "4") (name "/ECG.HR_LOD") (class "Default")
      (node (ref "TP1009") (pin "1") (pinfunction "1_1") (pintype "passive"))
      (node (ref "U1001") (pin "C1") (pinfunction "LOD_C1") (pintype "output"))
    )
    (net (code "5") (name "/ECG.HR_OUT") (class "Default")
      (node (ref "C1012") (pin "1") (pinfunction "1_1") (pintype "passive"))
      (node (ref "R1029") (pin "2") (pinfunction "2_2") (pintype "passive"))
      (node (ref "TP1010") (pin "1") (pinfunction "1_1") (pintype "passive"))
      (node (ref "U1001") (pin "D1") (pinfunction "OUT_D1") (pintype "output"))
    )
    (net (code "6") (name "/ECG.HR_SDNn") (class "Default")
      (node (ref "TP1001") (pin "1") (pinfunction "1_1") (pintype "passive"))
      (node (ref "U1001") (pin "B1") (pinfunction "~{SDN}_B1") (pintype "input"))
    )
    (net (code "7") (name "/ECG.RLD") (class "Default")
      (node (ref "TP1005") (pin "1") (pinfunction "1_1") (pintype "passive"))
      (node (ref "U1001") (pin "C2") (pinfunction "RLD_~{SDN}_C2") (pintype "input"))
      (node (ref "U1003") (pin "C2") (pinfunction "RLD_~{SDN}_C2") (pintype "input"))
    )
    (net (code "8") (name "/ECG.RR_LOD") (class "Default")
      (node (ref "TP1008") (pin "1") (pinfunction "1_1") (pintype "passive"))
      (node (ref "U1003") (pin "C1") (pinfunction "LOD_C1") (pintype "output"))
    )
    (net (code "9") (name "/ECG.RR_OUT") (class "Default")
      (node (ref "C1026") (pin "1") (pinfunction "1_1") (pintype "passive"))
      (node (ref "R1060") (pin "2") (pinfunction "2_2") (pintype "passive"))
      (node (ref "TP1012") (pin "1") (pinfunction "1_1") (pintype "passive"))
      (node (ref "U1003") (pin "D1") (pinfunction "OUT_D1") (pintype "output"))
    )
    (net (code "10") (name "/ECG.RR_SDNn") (class "Default")
      (node (ref "TP1004") (pin "1") (pinfunction "1_1") (pintype "passive"))
      (node (ref "U1003") (pin "B1") (pinfunction "~{SDN}_B1") (pintype "input"))
    )
    (net (code "11") (name "/ECG_HR+") (class "Default")
      (node (ref "R1012") (pin "1") (pinfunction "1_1") (pintype "passive"))
      (node (ref "R1020") (pin "1") (pinfunction "1_1") (pintype "passive"))
      (node (ref "TP1016") (pin "1") (pinfunction "1_1") (pintype "passive"))
    )
    (net (code "12") (name "/ECG_HR-") (class "Default")
      (node (ref "R1018") (pin "1") (pinfunction "1_1") (pintype "passive"))
      (node (ref "R1019") (pin "1") (pinfunction "1_1") (pintype "passive"))
      (node (ref "TP1017") (pin "1") (pinfunction "1_1") (pintype "passive"))
    )
    (net (code "13") (name "/ECG_HR_HPDRIVE") (class "Default")
      (node (ref "C1008") (pin "1") (pinfunction "1_1") (pintype "passive"))
      (node (ref "U1001") (pin "A5") (pinfunction "HPDRIVE_A5") (pintype "output"))
    )
    (net (code "14") (name "/ECG_HR_HPSENSE") (class "Default")
      (node (ref "C1008") (pin "2") (pinfunction "2_2") (pintype "passive"))
      (node (ref "R1009") (pin "2") (pinfunction "2_2") (pintype "passive"))
      (node (ref "U1001") (pin "A4") (pinfunction "HPSENSE_A4") (pintype "input"))
    )
    (net (code "15") (name "/ECG_HR_IN+") (class "Default")
      (node (ref "D1002") (pin "2") (pinfunction "A_2") (pintype "passive"))
      (node (ref "D1006") (pin "1") (pinfunction "K_1") (pintype "passive"))
      (node (ref "R1012") (pin "2") (pinfunction "2_2") (pintype "passive"))
      (node (ref "U1001") (pin "B5") (pinfunction "+IN_B5") (pintype "input"))
    )
    (net (code "16") (name "/ECG_HR_IN-") (class "Default")
      (node (ref "D1003") (pin "2") (pinfunction "A_2") (pintype "passive"))
      (node (ref "D1007") (pin "1") (pinfunction "K_1") (pintype "passive"))
      (node (ref "R1018") (pin "2") (pinfunction "2_2") (pintype "passive"))
      (node (ref "U1001") (pin "C5") (pinfunction "-IN_C5") (pintype "input"))
    )
    (net (code "17") (name "/ECG_HR_IOUT") (class "Default")
      (node (ref "R1004") (pin "1") (pinfunction "1_1") (pintype "passive"))
      (node (ref "R1023") (pin "1") (pinfunction "1_1") (pintype "passive"))
      (node (ref "U1001") (pin "B4") (pinfunction "IAOUT_B4") (pintype "output"))
    )
    (net (code "18") (name "/ECG_HR_OPAMP+") (class "Default")
      (node (ref "C1013") (pin "2") (pinfunction "2_2") (pintype "passive"))
      (node (ref "R1024") (pin "2") (pinfunction "2_2") (pintype "passive"))
      (node (ref "U1001") (pin "D3") (pinfunction "OPAMP+_D3") (pintype "input"))
    )
    (net (code "19") (name "/ECG_HR_OPAMP-") (class "Default")
      (node (ref "R1027") (pin "2") (pinfunction "2_2") (pintype "passive"))
      (node (ref "R1029") (pin "1") (pinfunction "1_1") (pintype "passive"))
      (node (ref "U1001") (pin "D2") (pinfunction "OPAMP-_D2") (pintype "input"))
    )
    (net (code "20") (name "/ECG_HR_REFIN") (class "Default")
      (node (ref "C1005") (pin "2") (pinfunction "2_2") (pintype "passive"))
      (node (ref "R1003") (pin "2") (pinfunction "2_2") (pintype "passive"))
      (node (ref "R1010") (pin "1") (pinfunction "1_1") (pintype "passive"))
      (node (ref "U1001") (pin "A3") (pinfunction "REFIN_A3") (pintype "input"))
    )
    (net (code "21") (name "/ECG_HR_REFOUT") (class "Default")
      (node (ref "C1002") (pin "1") (pinfunction "1_1") (pintype "passive"))
      (node (ref "C1013") (pin "1") (pinfunction "1_1") (pintype "passive"))
      (node (ref "R1027") (pin "1") (pinfunction "1_1") (pintype "passive"))
      (node (ref "U1001") (pin "C3") (pinfunction "REFOUT_C3") (pintype "output"))
    )
    (net (code "22") (name "/ECG_HR_RLD") (class "Default")
      (node (ref "C1010") (pin "1") (pinfunction "1_1") (pintype "passive"))
      (node (ref "R1022") (pin "2") (pinfunction "2_2") (pintype "passive"))
      (node (ref "U1001") (pin "D5") (pinfunction "RLD_D5") (pintype "output"))
    )
    (net (code "23") (name "/ECG_HR_RLDFB") (class "Default")
      (node (ref "C1010") (pin "2") (pinfunction "2_2") (pintype "passive"))
      (node (ref "U1001") (pin "C4") (pinfunction "RLDFB_C4") (pintype "input"))
    )
    (net (code "24") (name "/ECG_HR_SW") (class "Default")
      (node (ref "C1002") (pin "2") (pinfunction "2_2") (pintype "passive"))
      (node (ref "R1006") (pin "1") (pinfunction "1_1") (pintype "passive"))
      (node (ref "U1001") (pin "D4") (pinfunction "SW_D4") (pintype "passive"))
    )
    (net (code "25") (name "/ECG_RR+") (class "Default")
      (node (ref "R1043") (pin "1") (pinfunction "1_1") (pintype "passive"))
      (node (ref "R1051") (pin "1") (pinfunction "1_1") (pintype "passive"))
      (node (ref "TP1019") (pin "1") (pinfunction "1_1") (pintype "passive"))
    )
    (net (code "26") (name "/ECG_RR-") (class "Default")
      (node (ref "R1047") (pin "1") (pinfunction "1_1") (pintype "passive"))
      (node (ref "R1050") (pin "1") (pinfunction "1_1") (pintype "passive"))
      (node (ref "TP1021") (pin "1") (pinfunction "1_1") (pintype "passive"))
    )
    (net (code "27") (name "/ECG_RR_HPDRIVE") (class "Default")
      (node (ref "C1023") (pin "1") (pinfunction "1_1") (pintype "passive"))
      (node (ref "U1003") (pin "A5") (pinfunction "HPDRIVE_A5") (pintype "output"))
    )
    (net (code "28") (name "/ECG_RR_HPSENSE") (class "Default")
      (node (ref "C1023") (pin "2") (pinfunction "2_2") (pintype "passive"))
      (node (ref "R1040") (pin "1") (pinfunction "1_1") (pintype "passive"))
      (node (ref "U1003") (pin "A4") (pinfunction "HPSENSE_A4") (pintype "input"))
    )
    (net (code "29") (name "/ECG_RR_IN+") (class "Default")
      (node (ref "D1011") (pin "2") (pinfunction "A_2") (pintype "passive"))
      (node (ref "D1014") (pin "1") (pinfunction "K_1") (pintype "passive"))
      (node (ref "R1043") (pin "2") (pinfunction "2_2") (pintype "passive"))
      (node (ref "U1003") (pin "B5") (pinfunction "+IN_B5") (pintype "input"))
    )
    (net (code "30") (name "/ECG_RR_IN-") (class "Default")
      (node (ref "D1010") (pin "2") (pinfunction "A_2") (pintype "passive"))
      (node (ref "D1015") (pin "1") (pinfunction "K_1") (pintype "passive"))
      (node (ref "R1047") (pin "2") (pinfunction "2_2") (pintype "passive"))
      (node (ref "U1003") (pin "C5") (pinfunction "-IN_C5") (pintype "input"))
    )
    (net (code "31") (name "/ECG_RR_IOUT") (class "Default")
      (node (ref "R1035") (pin "2") (pinfunction "2_2") (pintype "passive"))
      (node (ref "R1054") (pin "1") (pinfunction "1_1") (pintype "passive"))
      (node (ref "U1003") (pin "B4") (pinfunction "IAOUT_B4") (pintype "output"))
    )
    (net (code "32") (name "/ECG_RR_OPAMP+") (class "Default")
      (node (ref "C1028") (pin "2") (pinfunction "2_2") (pintype "passive"))
      (node (ref "R1055") (pin "2") (pinfunction "2_2") (pintype "passive"))
      (node (ref "U1003") (pin "D3") (pinfunction "OPAMP+_D3") (pintype "input"))
    )
    (net (code "33") (name "/ECG_RR_OPAMP-") (class "Default")
      (node (ref "R1058") (pin "2") (pinfunction "2_2") (pintype "passive"))
      (node (ref "R1060") (pin "1") (pinfunction "1_1") (pintype "passive"))
      (node (ref "U1003") (pin "D2") (pinfunction "OPAMP-_D2") (pintype "input"))
    )
    (net (code "34") (name "/ECG_RR_REFIN") (class "Default")
      (node (ref "C1019") (pin "2") (pinfunction "2_2") (pintype "passive"))
      (node (ref "R1032") (pin "2") (pinfunction "2_2") (pintype "passive"))
      (node (ref "R1041") (pin "1") (pinfunction "1_1") (pintype "passive"))
      (node (ref "U1003") (pin "A3") (pinfunction "REFIN_A3") (pintype "input"))
    )
    (net (code "35") (name "/ECG_RR_REFOUT") (class "Default")
      (node (ref "C1017") (pin "2") (pinfunction "2_2") (pintype "passive"))
      (node (ref "C1028") (pin "1") (pinfunction "1_1") (pintype "passive"))
      (node (ref "R1058") (pin "1") (pinfunction "1_1") (pintype "passive"))
      (node (ref "U1003") (pin "C3") (pinfunction "REFOUT_C3") (pintype "output"))
    )
    (net (code "36") (name "/ECG_RR_RLD") (class "Default")
      (node (ref "C1025") (pin "1") (pinfunction "1_1") (pintype "passive"))
      (node (ref "R1053") (pin "2") (pinfunction "2_2") (pintype "passive"))
      (node (ref "U1003") (pin "D5") (pinfunction "RLD_D5") (pintype "output"))
    )
    (net (code "37") (name "/ECG_RR_RLDFB") (class "Default")
      (node (ref "C1025") (pin "2") (pinfunction "2_2") (pintype "passive"))
      (node (ref "U1003") (pin "C4") (pinfunction "RLDFB_C4") (pintype "input"))
    )
    (net (code "38") (name "/ECG_RR_SW") (class "Default")
      (node (ref "C1017") (pin "1") (pinfunction "1_1") (pintype "passive"))
      (node (ref "R1037") (pin "1") (pinfunction "1_1") (pintype "passive"))
      (node (ref "U1003") (pin "D4") (pinfunction "SW_D4") (pintype "passive"))
    )
    (net (code "39") (name "/ENG1+") (class "Default")
      (node (ref "R1011") (pin "1") (pinfunction "1_1") (pintype "passive"))
      (node (ref "R1017") (pin "1") (pinfunction "1_1") (pintype "passive"))
      (node (ref "TP1014") (pin "1") (pinfunction "1_1") (pintype "passive"))
    )
    (net (code "40") (name "/ENG1-") (class "Default")
      (node (ref "R1015") (pin "1") (pinfunction "1_1") (pintype "passive"))
      (node (ref "R1016") (pin "1") (pinfunction "1_1") (pintype "passive"))
      (node (ref "TP1015") (pin "1") (pinfunction "1_1") (pintype "passive"))
    )
    (net (code "41") (name "/ENG1.LOD") (class "Default")
      (node (ref "TP1006") (pin "1") (pinfunction "1_1") (pintype "passive"))
      (node (ref "U1000") (pin "12") (pinfunction "LOD+_12") (pintype "output"))
    )
    (net (code "42") (name "/ENG1.OUT") (class "Default")
      (node (ref "C1011") (pin "2") (pinfunction "2_2") (pintype "passive"))
      (node (ref "R1030") (pin "1") (pinfunction "1_1") (pintype "passive"))
      (node (ref "TP1011") (pin "1") (pinfunction "1_1") (pintype "passive"))
      (node (ref "U1000") (pin "10") (pinfunction "OUT_10") (pintype "output"))
    )
    (net (code "43") (name "/ENG1.SDNn") (class "Default")
      (node (ref "TP1000") (pin "1") (pinfunction "1_1") (pintype "passive"))
      (node (ref "U1000") (pin "13") (pinfunction "~{SDN}_13") (pintype "input"))
    )
    (net (code "44") (name "/ENG1_HPDRIVE") (class "Default")
      (node (ref "C1007") (pin "1") (pinfunction "1_1") (pintype "passive"))
      (node (ref "U1000") (pin "1") (pinfunction "HPDRIVE_1") (pintype "output"))
    )
    (net (code "45") (name "/ENG1_HPSENSE") (class "Default")
      (node (ref "C1007") (pin "2") (pinfunction "2_2") (pintype "passive"))
      (node (ref "R1007") (pin "1") (pinfunction "1_1") (pintype "passive"))
      (node (ref "U1000") (pin "20") (pinfunction "HPSENSE_20") (pintype "input"))
    )
    (net (code "46") (name "/ENG1_IN+") (class "Default")
      (node (ref "D1000") (pin "2") (pinfunction "A_2") (pintype "passive"))
      (node (ref "D1004") (pin "1") (pinfunction "K_1") (pintype "passive"))
      (node (ref "R1011") (pin "2") (pinfunction "2_2") (pintype "passive"))
      (node (ref "U1000") (pin "2") (pinfunction "+IN_2") (pintype "tri_state"))
    )
    (net (code "47") (name "/ENG1_IN-") (class "Default")
      (node (ref "D1001") (pin "2") (pinfunction "A_2") (pintype "passive"))
      (node (ref "D1005") (pin "1") (pinfunction "K_1") (pintype "passive"))
      (node (ref "R1015") (pin "2") (pinfunction "2_2") (pintype "passive"))
      (node (ref "U1000") (pin "3") (pinfunction "-IN_3") (pintype "tri_state"))
    )
    (net (code "48") (name "/ENG1_IOUT") (class "Default")
      (node (ref "C1000") (pin "2") (pinfunction "2_2") (pintype "passive"))
      (node (ref "R1002") (pin "2") (pinfunction "2_2") (pintype "passive"))
      (node (ref "U1000") (pin "19") (pinfunction "IAOUT_19") (pintype "passive"))
    )
    (net (code "49") (name "/ENG1_OPAMP+") (class "Default")
      (node (ref "C1014") (pin "2") (pinfunction "2_2") (pintype "passive"))
      (node (ref "R1026") (pin "2") (pinfunction "2_2") (pintype "passive"))
      (node (ref "U1000") (pin "7") (pinfunction "OPAMP+_7") (pintype "tri_state"))
    )
    (net (code "50") (name "/ENG1_OPAMP-") (class "Default")
      (node (ref "R1028") (pin "2") (pinfunction "2_2") (pintype "passive"))
      (node (ref "R1030") (pin "2") (pinfunction "2_2") (pintype "passive"))
      (node (ref "U1000") (pin "9") (pinfunction "OPAMP-_9") (pintype "tri_state"))
    )
    (net (code "51") (name "/ENG1_REFIN") (class "Default")
      (node (ref "C1003") (pin "2") (pinfunction "2_2") (pintype "passive"))
      (node (ref "R1000") (pin "2") (pinfunction "2_2") (pintype "passive"))
      (node (ref "R1008") (pin "1") (pinfunction "1_1") (pintype "passive"))
      (node (ref "U1000") (pin "18") (pinfunction "REFIN_18") (pintype "input"))
    )
    (net (code "52") (name "/ENG1_REFOUT") (class "Default")
      (node (ref "C1001") (pin "2") (pinfunction "2_2") (pintype "passive"))
      (node (ref "C1014") (pin "1") (pinfunction "1_1") (pintype "passive"))
      (node (ref "R1001") (pin "1") (pinfunction "1_1") (pintype "passive"))
      (node (ref "R1028") (pin "1") (pinfunction "1_1") (pintype "passive"))
      (node (ref "U1000") (pin "8") (pinfunction "REFOUT_8") (pintype "passive"))
    )
    (net (code "53") (name "/ENG1_RLD") (class "Default")
      (node (ref "C1009") (pin "1") (pinfunction "1_1") (pintype "passive"))
      (node (ref "R1021") (pin "2") (pinfunction "2_2") (pintype "passive"))
      (node (ref "U1000") (pin "5") (pinfunction "RLD_5") (pintype "passive"))
    )
    (net (code "54") (name "/ENG1_RLDFB") (class "Default")
      (node (ref "C1009") (pin "2") (pinfunction "2_2") (pintype "passive"))
      (node (ref "U1000") (pin "4") (pinfunction "RLDFB_4") (pintype "passive"))
    )
    (net (code "55") (name "/ENG1_SW") (class "Default")
      (node (ref "C1001") (pin "1") (pinfunction "1_1") (pintype "passive"))
      (node (ref "R1005") (pin "1") (pinfunction "1_1") (pintype "passive"))
      (node (ref "U1000") (pin "6") (pinfunction "SW_6") (pintype "passive"))
    )
    (net (code "56") (name "/ENG1_VO1") (class "Default")
      (node (ref "C1000") (pin "1") (pinfunction "1_1") (pintype "passive"))
      (node (ref "R1001") (pin "2") (pinfunction "2_2") (pintype "passive"))
      (node (ref "R1025") (pin "1") (pinfunction "1_1") (pintype "passive"))
    )
    (net (code "57") (name "/ENG2+") (class "Default")
      (node (ref "R1042") (pin "1") (pinfunction "1_1") (pintype "passive"))
      (node (ref "R1049") (pin "1") (pinfunction "1_1") (pintype "passive"))
      (node (ref "TP1018") (pin "1") (pinfunction "1_1") (pintype "passive"))
    )
    (net (code "58") (name "/ENG2-") (class "Default")
      (node (ref "R1046") (pin "1") (pinfunction "1_1") (pintype "passive"))
      (node (ref "R1048") (pin "1") (pinfunction "1_1") (pintype "passive"))
      (node (ref "TP1020") (pin "1") (pinfunction "1_1") (pintype "passive"))
    )
    (net (code "59") (name "/ENG2.LOD") (class "Default")
      (node (ref "TP1007") (pin "1") (pinfunction "1_1") (pintype "passive"))
      (node (ref "U1002") (pin "12") (pinfunction "LOD+_12") (pintype "output"))
    )
    (net (code "60") (name "/ENG2.OUT") (class "Default")
      (node (ref "C1027") (pin "2") (pinfunction "2_2") (pintype "passive"))
      (node (ref "R1061") (pin "1") (pinfunction "1_1") (pintype "passive"))
      (node (ref "TP1013") (pin "1") (pinfunction "1_1") (pintype "passive"))
      (node (ref "U1002") (pin "10") (pinfunction "OUT_10") (pintype "output"))
    )
    (net (code "61") (name "/ENG2.SDNn") (class "Default")
      (node (ref "TP1003") (pin "1") (pinfunction "1_1") (pintype "passive"))
      (node (ref "U1002") (pin "13") (pinfunction "~{SDN}_13") (pintype "input"))
    )
    (net (code "62") (name "/ENG2_HPDRIVE") (class "Default")
      (node (ref "C1022") (pin "1") (pinfunction "1_1") (pintype "passive"))
      (node (ref "U1002") (pin "1") (pinfunction "HPDRIVE_1") (pintype "output"))
    )
    (net (code "63") (name "/ENG2_HPSENSE") (class "Default")
      (node (ref "C1022") (pin "2") (pinfunction "2_2") (pintype "passive"))
      (node (ref "R1038") (pin "1") (pinfunction "1_1") (pintype "passive"))
      (node (ref "U1002") (pin "20") (pinfunction "HPSENSE_20") (pintype "input"))
    )
    (net (code "64") (name "/ENG2_IN+") (class "Default")
      (node (ref "D1008") (pin "2") (pinfunction "A_2") (pintype "passive"))
      (node (ref "D1012") (pin "1") (pinfunction "K_1") (pintype "passive"))
      (node (ref "R1042") (pin "2") (pinfunction "2_2") (pintype "passive"))
      (node (ref "U1002") (pin "2") (pinfunction "+IN_2") (pintype "tri_state"))
    )
    (net (code "65") (name "/ENG2_IN-") (class "Default")
      (node (ref "D1009") (pin "2") (pinfunction "A_2") (pintype "passive"))
      (node (ref "D1013") (pin "1") (pinfunction "K_1") (pintype "passive"))
      (node (ref "R1046") (pin "2") (pinfunction "2_2") (pintype "passive"))
      (node (ref "U1002") (pin "3") (pinfunction "-IN_3") (pintype "tri_state"))
    )
    (net (code "66") (name "/ENG2_IOUT") (class "Default")
      (node (ref "C1015") (pin "2") (pinfunction "2_2") (pintype "passive"))
      (node (ref "R1034") (pin "2") (pinfunction "2_2") (pintype "passive"))
      (node (ref "U1002") (pin "19") (pinfunction "IAOUT_19") (pintype "passive"))
    )
    (net (code "67") (name "/ENG2_OPAMP+") (class "Default")
      (node (ref "C1029") (pin "2") (pinfunction "2_2") (pintype "passive"))
      (node (ref "R1057") (pin "2") (pinfunction "2_2") (pintype "passive"))
      (node (ref "U1002") (pin "7") (pinfunction "OPAMP+_7") (pintype "tri_state"))
    )
    (net (code "68") (name "/ENG2_OPAMP-") (class "Default")
      (node (ref "R1059") (pin "2") (pinfunction "2_2") (pintype "passive"))
      (node (ref "R1061") (pin "2") (pinfunction "2_2") (pintype "passive"))
      (node (ref "U1002") (pin "9") (pinfunction "OPAMP-_9") (pintype "tri_state"))
    )
    (net (code "69") (name "/ENG2_REFIN") (class "Default")
      (node (ref "C1018") (pin "1") (pinfunction "1_1") (pintype "passive"))
      (node (ref "R1031") (pin "1") (pinfunction "1_1") (pintype "passive"))
      (node (ref "R1039") (pin "2") (pinfunction "2_2") (pintype "passive"))
      (node (ref "U1002") (pin "18") (pinfunction "REFIN_18") (pintype "input"))
    )
    (net (code "70") (name "/ENG2_REFOUT") (class "Default")
      (node (ref "C1016") (pin "2") (pinfunction "2_2") (pintype "passive"))
      (node (ref "C1029") (pin "1") (pinfunction "1_1") (pintype "passive"))
      (node (ref "R1033") (pin "1") (pinfunction "1_1") (pintype "passive"))
      (node (ref "R1059") (pin "1") (pinfunction "1_1") (pintype "passive"))
      (node (ref "U1002") (pin "8") (pinfunction "REFOUT_8") (pintype "passive"))
    )
    (net (code "71") (name "/ENG2_RLD") (class "Default")
      (node (ref "C1024") (pin "1") (pinfunction "1_1") (pintype "passive"))
      (node (ref "R1052") (pin "2") (pinfunction "2_2") (pintype "passive"))
      (node (ref "U1002") (pin "5") (pinfunction "RLD_5") (pintype "passive"))
    )
    (net (code "72") (name "/ENG2_RLDFB") (class "Default")
      (node (ref "C1024") (pin "2") (pinfunction "2_2") (pintype "passive"))
      (node (ref "U1002") (pin "4") (pinfunction "RLDFB_4") (pintype "passive"))
    )
    (net (code "73") (name "/ENG2_SW") (class "Default")
      (node (ref "C1016") (pin "1") (pinfunction "1_1") (pintype "passive"))
      (node (ref "R1036") (pin "1") (pinfunction "1_1") (pintype "passive"))
      (node (ref "U1002") (pin "6") (pinfunction "SW_6") (pintype "passive"))
    )
    (net (code "74") (name "/ENG2_VO1") (class "Default")
      (node (ref "C1015") (pin "1") (pinfunction "1_1") (pintype "passive"))
      (node (ref "R1033") (pin "2") (pinfunction "2_2") (pintype "passive"))
      (node (ref "R1056") (pin "1") (pinfunction "1_1") (pintype "passive"))
    )
    (net (code "77") (name "GND") (class "Default")
      (node (ref "C1003") (pin "1") (pinfunction "1_1") (pintype "passive"))
      (node (ref "C1004") (pin "1") (pinfunction "1_1") (pintype "passive"))
      (node (ref "C1005") (pin "1") (pinfunction "1_1") (pintype "passive"))
      (node (ref "C1006") (pin "1") (pinfunction "1_1") (pintype "passive"))
      (node (ref "C1018") (pin "2") (pinfunction "2_2") (pintype "passive"))
      (node (ref "C1019") (pin "1") (pinfunction "1_1") (pintype "passive"))
      (node (ref "C1020") (pin "1") (pinfunction "1_1") (pintype "passive"))
      (node (ref "C1021") (pin "2") (pinfunction "2_2") (pintype "passive"))
      (node (ref "D1004") (pin "2") (pinfunction "A_2") (pintype "passive"))
      (node (ref "D1005") (pin "2") (pinfunction "A_2") (pintype "passive"))
      (node (ref "D1006") (pin "2") (pinfunction "A_2") (pintype "passive"))
      (node (ref "D1007") (pin "2") (pinfunction "A_2") (pintype "passive"))
      (node (ref "D1012") (pin "2") (pinfunction "A_2") (pintype "passive"))
      (node (ref "D1013") (pin "2") (pinfunction "A_2") (pintype "passive"))
      (node (ref "D1014") (pin "2") (pinfunction "A_2") (pintype "passive"))
      (node (ref "D1015") (pin "2") (pinfunction "A_2") (pintype "passive"))
      (node (ref "R1008") (pin "2") (pinfunction "2_2") (pintype "passive"))
      (node (ref "R1010") (pin "2") (pinfunction "2_2") (pintype "passive"))
      (node (ref "R1039") (pin "1") (pinfunction "1_1") (pintype "passive"))
      (node (ref "R1041") (pin "2") (pinfunction "2_2") (pintype "passive"))
      (node (ref "U1000") (pin "16") (pinfunction "GND_16") (pintype "power_in"))
      (node (ref "U1000") (pin "21") (pinfunction "EP_21") (pintype "power_in"))
      (node (ref "U1001") (pin "A1") (pinfunction "GND_A1") (pintype "power_in"))
      (node (ref "U1002") (pin "16") (pinfunction "GND_16") (pintype "power_in"))
      (node (ref "U1002") (pin "21") (pinfunction "EP_21") (pintype "power_in"))
      (node (ref "U1003") (pin "A1") (pinfunction "GND_A1") (pintype "power_in"))
    )
    (net (code "78") (name "Net-(C1011-Pad1)") (class "Default")
      (node (ref "C1011") (pin "1") (pinfunction "1_1") (pintype "passive"))
      (node (ref "R1025") (pin "2") (pinfunction "2_2") (pintype "passive"))
      (node (ref "R1026") (pin "1") (pinfunction "1_1") (pintype "passive"))
    )
    (net (code "79") (name "Net-(C1012-Pad2)") (class "Default")
      (node (ref "C1012") (pin "2") (pinfunction "2_2") (pintype "passive"))
      (node (ref "R1023") (pin "2") (pinfunction "2_2") (pintype "passive"))
      (node (ref "R1024") (pin "1") (pinfunction "1_1") (pintype "passive"))
    )
    (net (code "80") (name "Net-(C1026-Pad2)") (class "Default")
      (node (ref "C1026") (pin "2") (pinfunction "2_2") (pintype "passive"))
      (node (ref "R1054") (pin "2") (pinfunction "2_2") (pintype "passive"))
      (node (ref "R1055") (pin "1") (pinfunction "1_1") (pintype "passive"))
    )
    (net (code "81") (name "Net-(C1027-Pad1)") (class "Default")
      (node (ref "C1027") (pin "1") (pinfunction "1_1") (pintype "passive"))
      (node (ref "R1056") (pin "2") (pinfunction "2_2") (pintype "passive"))
      (node (ref "R1057") (pin "1") (pinfunction "1_1") (pintype "passive"))
    )
    (net (code "82") (name "Net-(R1002-Pad1)") (class "Default")
      (node (ref "R1002") (pin "1") (pinfunction "1_1") (pintype "passive"))
      (node (ref "R1005") (pin "2") (pinfunction "2_2") (pintype "passive"))
      (node (ref "R1007") (pin "2") (pinfunction "2_2") (pintype "passive"))
    )
    (net (code "83") (name "Net-(R1004-Pad2)") (class "Default")
      (node (ref "R1004") (pin "2") (pinfunction "2_2") (pintype "passive"))
      (node (ref "R1006") (pin "2") (pinfunction "2_2") (pintype "passive"))
      (node (ref "R1009") (pin "1") (pinfunction "1_1") (pintype "passive"))
    )
    (net (code "84") (name "Net-(R1016-Pad2)") (class "Default")
      (node (ref "R1016") (pin "2") (pinfunction "2_2") (pintype "passive"))
      (node (ref "R1017") (pin "2") (pinfunction "2_2") (pintype "passive"))
      (node (ref "R1021") (pin "1") (pinfunction "1_1") (pintype "passive"))
    )
    (net (code "85") (name "Net-(R1019-Pad2)") (class "Default")
      (node (ref "R1019") (pin "2") (pinfunction "2_2") (pintype "passive"))
      (node (ref "R1020") (pin "2") (pinfunction "2_2") (pintype "passive"))
      (node (ref "R1022") (pin "1") (pinfunction "1_1") (pintype "passive"))
    )
    (net (code "86") (name "Net-(R1034-Pad1)") (class "Default")
      (node (ref "R1034") (pin "1") (pinfunction "1_1") (pintype "passive"))
      (node (ref "R1036") (pin "2") (pinfunction "2_2") (pintype "passive"))
      (node (ref "R1038") (pin "2") (pinfunction "2_2") (pintype "passive"))
    )
    (net (code "87") (name "Net-(R1035-Pad1)") (class "Default")
      (node (ref "R1035") (pin "1") (pinfunction "1_1") (pintype "passive"))
      (node (ref "R1037") (pin "2") (pinfunction "2_2") (pintype "passive"))
      (node (ref "R1040") (pin "2") (pinfunction "2_2") (pintype "passive"))
    )
    (net (code "88") (name "Net-(R1048-Pad2)") (class "Default")
      (node (ref "R1048") (pin "2") (pinfunction "2_2") (pintype "passive"))
      (node (ref "R1049") (pin "2") (pinfunction "2_2") (pintype "passive"))
      (node (ref "R1052") (pin "1") (pinfunction "1_1") (pintype "passive"))
    )
    (net (code "89") (name "Net-(R1050-Pad2)") (class "Default")
      (node (ref "R1050") (pin "2") (pinfunction "2_2") (pintype "passive"))
      (node (ref "R1051") (pin "2") (pinfunction "2_2") (pintype "passive"))
      (node (ref "R1053") (pin "1") (pinfunction "1_1") (pintype "passive"))
    )
    (net (code "90") (name "Net-(U1000A-AC{slash}~{DC})") (class "Default")
      (node (ref "R1014") (pin "1") (pinfunction "1_1") (pintype "passive"))
      (node (ref "U1000") (pin "14") (pinfunction "AC/~{DC}_14") (pintype "input"))
    )
    (net (code "91") (name "Net-(U1001A-AC_{slash}_~{DC})") (class "Default")
      (node (ref "R1013") (pin "1") (pinfunction "1_1") (pintype "passive"))
      (node (ref "U1001") (pin "B2") (pinfunction "AC_/_~{DC}_B2") (pintype "input"))
    )
    (net (code "92") (name "Net-(U1002A-AC{slash}~{DC})") (class "Default")
      (node (ref "R1045") (pin "1") (pinfunction "1_1") (pintype "passive"))
      (node (ref "U1002") (pin "14") (pinfunction "AC/~{DC}_14") (pintype "input"))
    )
    (net (code "93") (name "Net-(U1003A-AC_{slash}_~{DC})") (class "Default")
      (node (ref "R1044") (pin "1") (pinfunction "1_1") (pintype "passive"))
      (node (ref "U1003") (pin "B2") (pinfunction "AC_/_~{DC}_B2") (pintype "input"))
    )
    (net (code "94") (name "unconnected-(U1000A-LOD--Pad11)") (class "Default")
      (node (ref "U1000") (pin "11") (pinfunction "LOD-_11") (pintype "output+no_connect"))
    )
    (net (code "95") (name "unconnected-(U1002A-LOD--Pad11)") (class "Default")
      (node (ref "U1002") (pin "11") (pinfunction "LOD-_11") (pintype "output+no_connect"))
    )
  )
)
